# DC075B_ANALOG_INPUTS.net
KiCad netlist of a schematic drawn in Altium Designer
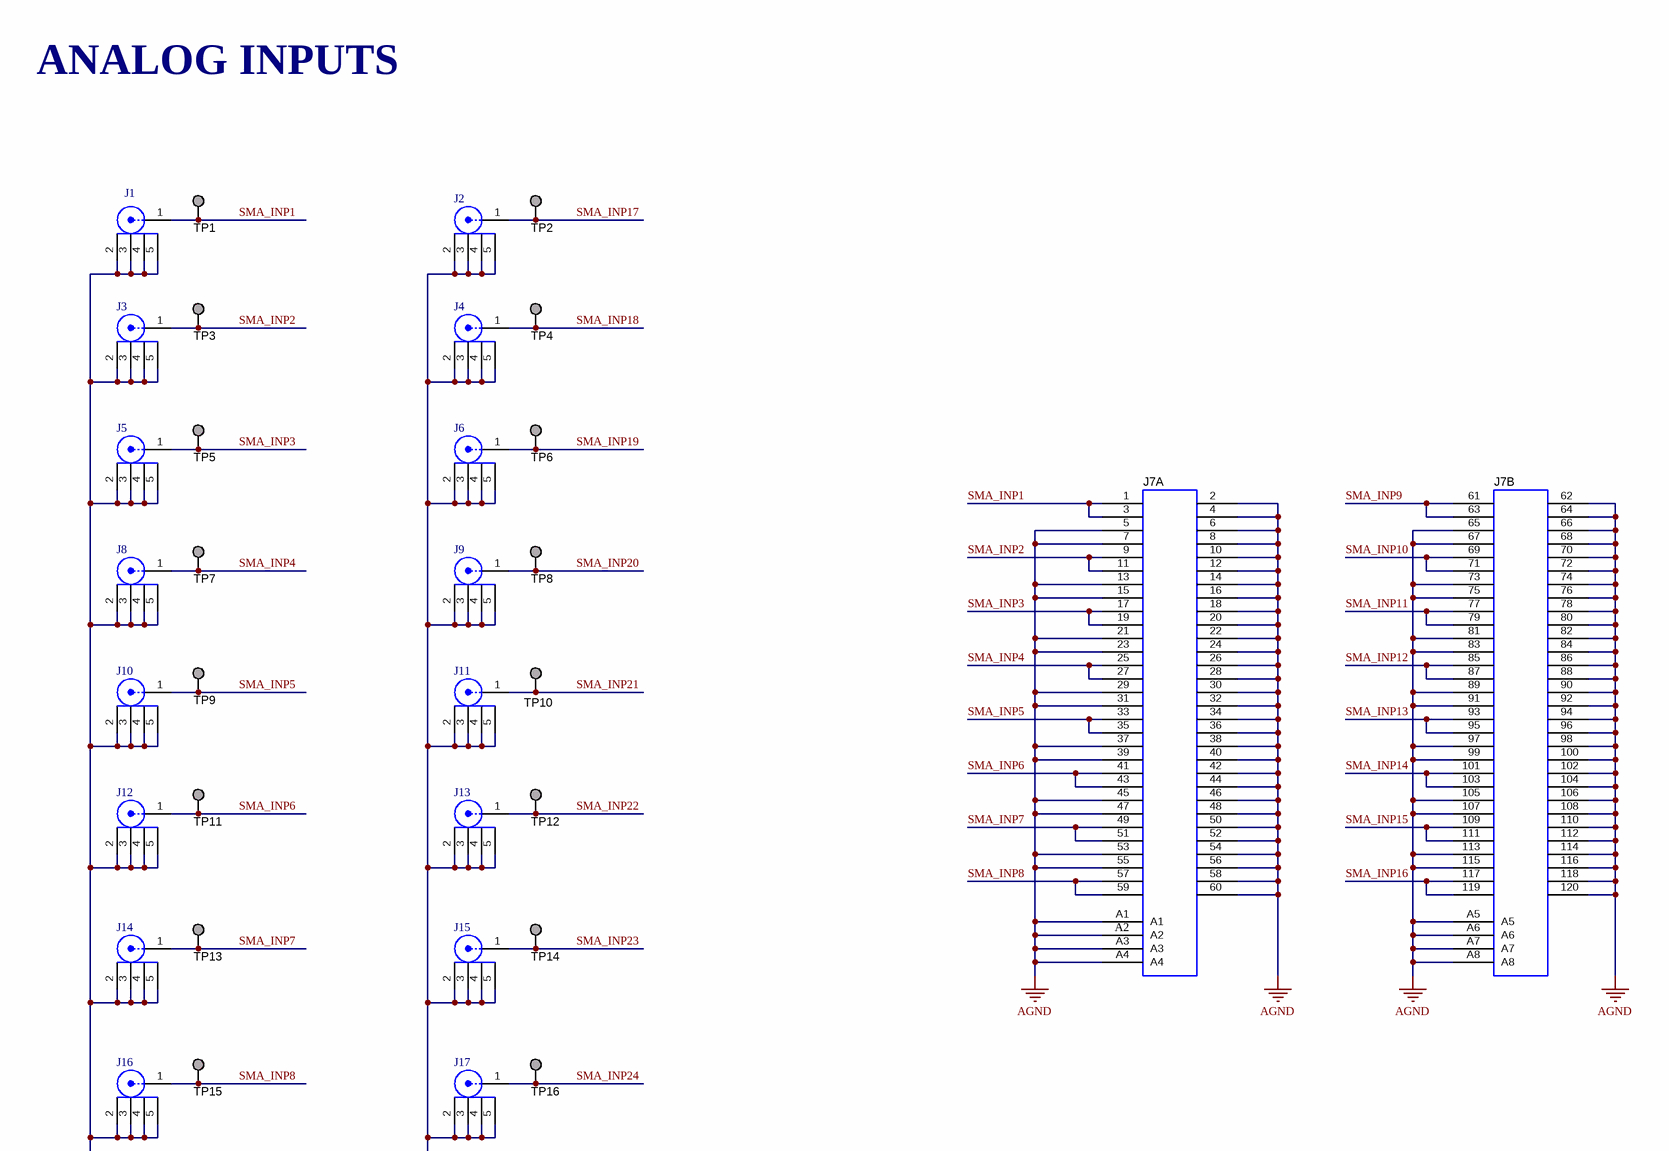
[diagram p0: DC075B_ANALOG_INPUTS.SchDoc, top left]
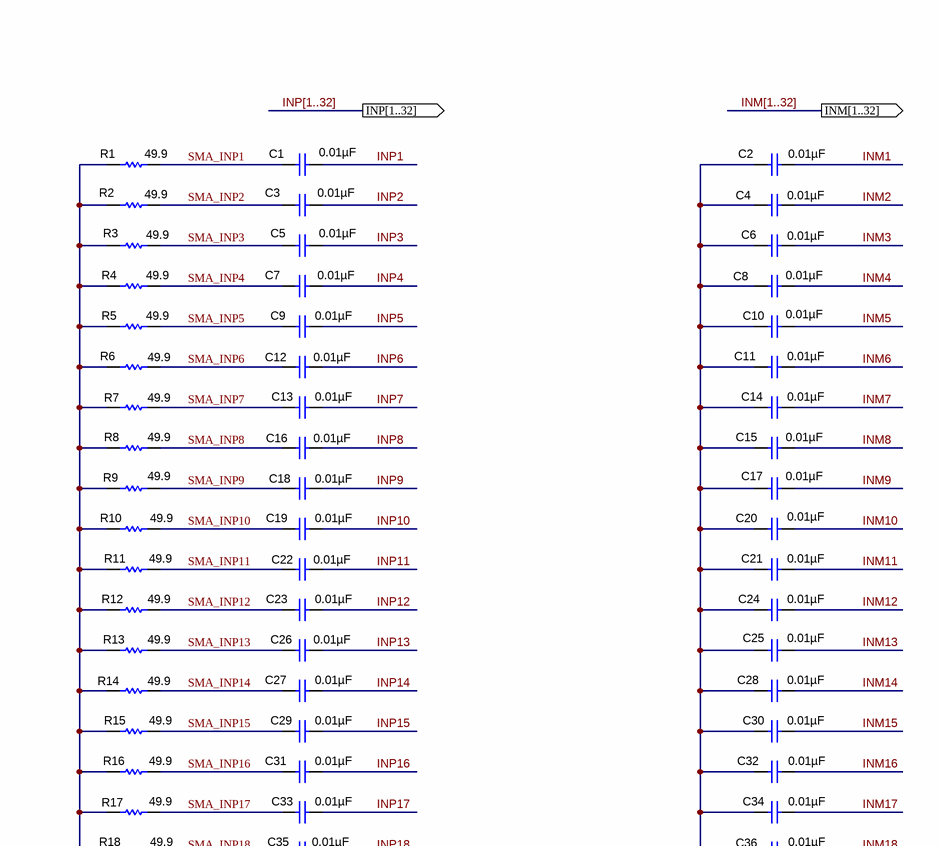
[diagram p1: DC075B_ANALOG_INPUTS.SchDoc, top right]
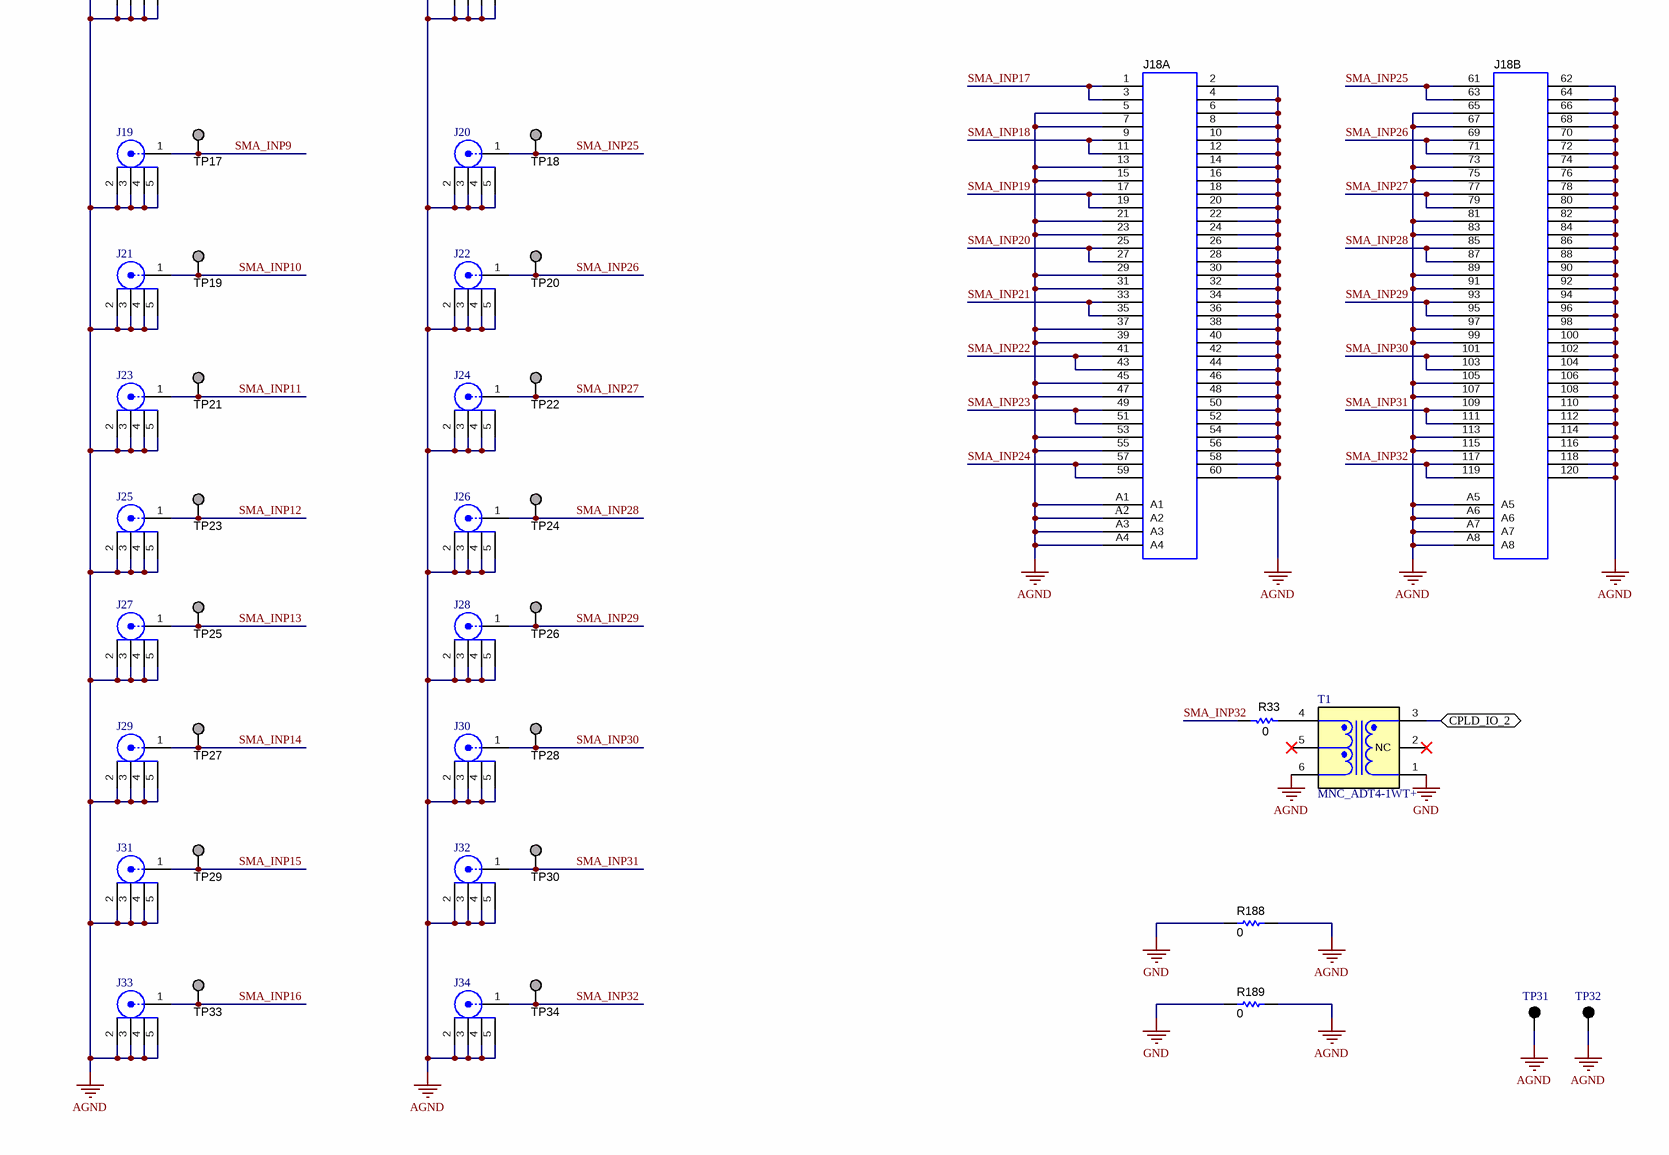
[diagram p2: DC075B_ANALOG_INPUTS.SchDoc, bottom left]
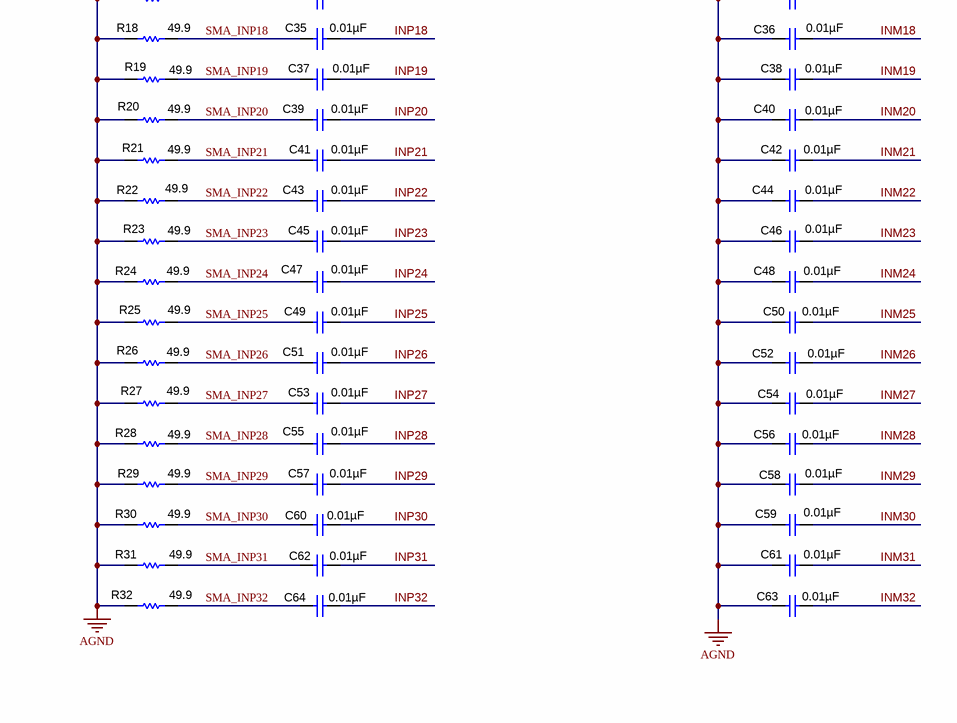
[diagram p3: DC075B_ANALOG_INPUTS.SchDoc, bottom right]

(export (version "E")
  (design (tool "Eeschema 10.0.6"))
  (components
    (comp (ref "C1")
      (value "04023C103JAT2A")
      (footprint "0402")
      (description "CAP, CERM, 0.01 µF, 25 V,+/- 5%, X7R, 0402")
      (fields (field (name "VALUEDISPLAYED") "0.01µF") (field (name "MANUFACTURER") "AVX"))
      (libsource (lib "Altium Vault - TI") (part "Capacitor"))
    )
    (comp (ref "C2")
      (value "04023C103JAT2A")
      (footprint "0402")
      (description "CAP, CERM, 0.01 µF, 25 V,+/- 5%, X7R, 0402")
      (fields (field (name "VALUEDISPLAYED") "0.01µF") (field (name "MANUFACTURER") "AVX"))
      (libsource (lib "Altium Vault - TI") (part "Capacitor"))
    )
    (comp (ref "C3")
      (value "04023C103JAT2A")
      (footprint "0402")
      (description "CAP, CERM, 0.01 µF, 25 V,+/- 5%, X7R, 0402")
      (fields (field (name "VALUEDISPLAYED") "0.01µF") (field (name "MANUFACTURER") "AVX"))
      (libsource (lib "Altium Vault - TI") (part "Capacitor"))
    )
    (comp (ref "C4")
      (value "04023C103JAT2A")
      (footprint "0402")
      (description "CAP, CERM, 0.01 µF, 25 V,+/- 5%, X7R, 0402")
      (fields (field (name "VALUEDISPLAYED") "0.01µF") (field (name "MANUFACTURER") "AVX"))
      (libsource (lib "Altium Vault - TI") (part "Capacitor"))
    )
    (comp (ref "C5")
      (value "04023C103JAT2A")
      (footprint "0402")
      (description "CAP, CERM, 0.01 µF, 25 V,+/- 5%, X7R, 0402")
      (fields (field (name "VALUEDISPLAYED") "0.01µF") (field (name "MANUFACTURER") "AVX"))
      (libsource (lib "Altium Vault - TI") (part "Capacitor"))
    )
    (comp (ref "C6")
      (value "04023C103JAT2A")
      (footprint "0402")
      (description "CAP, CERM, 0.01 µF, 25 V,+/- 5%, X7R, 0402")
      (fields (field (name "VALUEDISPLAYED") "0.01µF") (field (name "MANUFACTURER") "AVX"))
      (libsource (lib "Altium Vault - TI") (part "Capacitor"))
    )
    (comp (ref "C7")
      (value "04023C103JAT2A")
      (footprint "0402")
      (description "CAP, CERM, 0.01 µF, 25 V,+/- 5%, X7R, 0402")
      (fields (field (name "VALUEDISPLAYED") "0.01µF") (field (name "MANUFACTURER") "AVX"))
      (libsource (lib "Altium Vault - TI") (part "Capacitor"))
    )
    (comp (ref "C8")
      (value "04023C103JAT2A")
      (footprint "0402")
      (description "CAP, CERM, 0.01 µF, 25 V,+/- 5%, X7R, 0402")
      (fields (field (name "VALUEDISPLAYED") "0.01µF") (field (name "MANUFACTURER") "AVX"))
      (libsource (lib "Altium Vault - TI") (part "Capacitor"))
    )
    (comp (ref "C9")
      (value "04023C103JAT2A")
      (footprint "0402")
      (description "CAP, CERM, 0.01 µF, 25 V,+/- 5%, X7R, 0402")
      (fields (field (name "VALUEDISPLAYED") "0.01µF") (field (name "MANUFACTURER") "AVX"))
      (libsource (lib "Altium Vault - TI") (part "Capacitor"))
    )
    (comp (ref "C10")
      (value "04023C103JAT2A")
      (footprint "0402")
      (description "CAP, CERM, 0.01 µF, 25 V,+/- 5%, X7R, 0402")
      (fields (field (name "VALUEDISPLAYED") "0.01µF") (field (name "MANUFACTURER") "AVX"))
      (libsource (lib "Altium Vault - TI") (part "Capacitor"))
    )
    (comp (ref "C11")
      (value "04023C103JAT2A")
      (footprint "0402")
      (description "CAP, CERM, 0.01 µF, 25 V,+/- 5%, X7R, 0402")
      (fields (field (name "VALUEDISPLAYED") "0.01µF") (field (name "MANUFACTURER") "AVX"))
      (libsource (lib "Altium Vault - TI") (part "Capacitor"))
    )
    (comp (ref "C12")
      (value "04023C103JAT2A")
      (footprint "0402")
      (description "CAP, CERM, 0.01 µF, 25 V,+/- 5%, X7R, 0402")
      (fields (field (name "VALUEDISPLAYED") "0.01µF") (field (name "MANUFACTURER") "AVX"))
      (libsource (lib "Altium Vault - TI") (part "Capacitor"))
    )
    (comp (ref "C13")
      (value "04023C103JAT2A")
      (footprint "0402")
      (description "CAP, CERM, 0.01 µF, 25 V,+/- 5%, X7R, 0402")
      (fields (field (name "VALUEDISPLAYED") "0.01µF") (field (name "MANUFACTURER") "AVX"))
      (libsource (lib "Altium Vault - TI") (part "Capacitor"))
    )
    (comp (ref "C14")
      (value "04023C103JAT2A")
      (footprint "0402")
      (description "CAP, CERM, 0.01 µF, 25 V,+/- 5%, X7R, 0402")
      (fields (field (name "VALUEDISPLAYED") "0.01µF") (field (name "MANUFACTURER") "AVX"))
      (libsource (lib "Altium Vault - TI") (part "Capacitor"))
    )
    (comp (ref "C15")
      (value "04023C103JAT2A")
      (footprint "0402")
      (description "CAP, CERM, 0.01 µF, 25 V,+/- 5%, X7R, 0402")
      (fields (field (name "VALUEDISPLAYED") "0.01µF") (field (name "MANUFACTURER") "AVX"))
      (libsource (lib "Altium Vault - TI") (part "Capacitor"))
    )
    (comp (ref "C16")
      (value "04023C103JAT2A")
      (footprint "0402")
      (description "CAP, CERM, 0.01 µF, 25 V,+/- 5%, X7R, 0402")
      (fields (field (name "VALUEDISPLAYED") "0.01µF") (field (name "MANUFACTURER") "AVX"))
      (libsource (lib "Altium Vault - TI") (part "Capacitor"))
    )
    (comp (ref "C17")
      (value "04023C103JAT2A")
      (footprint "0402")
      (description "CAP, CERM, 0.01 µF, 25 V,+/- 5%, X7R, 0402")
      (fields (field (name "VALUEDISPLAYED") "0.01µF") (field (name "MANUFACTURER") "AVX"))
      (libsource (lib "Altium Vault - TI") (part "Capacitor"))
    )
    (comp (ref "C18")
      (value "04023C103JAT2A")
      (footprint "0402")
      (description "CAP, CERM, 0.01 µF, 25 V,+/- 5%, X7R, 0402")
      (fields (field (name "VALUEDISPLAYED") "0.01µF") (field (name "MANUFACTURER") "AVX"))
      (libsource (lib "Altium Vault - TI") (part "Capacitor"))
    )
    (comp (ref "C19")
      (value "04023C103JAT2A")
      (footprint "0402")
      (description "CAP, CERM, 0.01 µF, 25 V,+/- 5%, X7R, 0402")
      (fields (field (name "VALUEDISPLAYED") "0.01µF") (field (name "MANUFACTURER") "AVX"))
      (libsource (lib "Altium Vault - TI") (part "Capacitor"))
    )
    (comp (ref "C20")
      (value "04023C103JAT2A")
      (footprint "0402")
      (description "CAP, CERM, 0.01 µF, 25 V,+/- 5%, X7R, 0402")
      (fields (field (name "VALUEDISPLAYED") "0.01µF") (field (name "MANUFACTURER") "AVX"))
      (libsource (lib "Altium Vault - TI") (part "Capacitor"))
    )
    (comp (ref "C21")
      (value "04023C103JAT2A")
      (footprint "0402")
      (description "CAP, CERM, 0.01 µF, 25 V,+/- 5%, X7R, 0402")
      (fields (field (name "VALUEDISPLAYED") "0.01µF") (field (name "MANUFACTURER") "AVX"))
      (libsource (lib "Altium Vault - TI") (part "Capacitor"))
    )
    (comp (ref "C22")
      (value "04023C103JAT2A")
      (footprint "0402")
      (description "CAP, CERM, 0.01 µF, 25 V,+/- 5%, X7R, 0402")
      (fields (field (name "VALUEDISPLAYED") "0.01µF") (field (name "MANUFACTURER") "AVX"))
      (libsource (lib "Altium Vault - TI") (part "Capacitor"))
    )
    (comp (ref "C23")
      (value "04023C103JAT2A")
      (footprint "0402")
      (description "CAP, CERM, 0.01 µF, 25 V,+/- 5%, X7R, 0402")
      (fields (field (name "VALUEDISPLAYED") "0.01µF") (field (name "MANUFACTURER") "AVX"))
      (libsource (lib "Altium Vault - TI") (part "Capacitor"))
    )
    (comp (ref "C24")
      (value "04023C103JAT2A")
      (footprint "0402")
      (description "CAP, CERM, 0.01 µF, 25 V,+/- 5%, X7R, 0402")
      (fields (field (name "VALUEDISPLAYED") "0.01µF") (field (name "MANUFACTURER") "AVX"))
      (libsource (lib "Altium Vault - TI") (part "Capacitor"))
    )
    (comp (ref "C25")
      (value "04023C103JAT2A")
      (footprint "0402")
      (description "CAP, CERM, 0.01 µF, 25 V,+/- 5%, X7R, 0402")
      (fields (field (name "VALUEDISPLAYED") "0.01µF") (field (name "MANUFACTURER") "AVX"))
      (libsource (lib "Altium Vault - TI") (part "Capacitor"))
    )
    (comp (ref "C26")
      (value "04023C103JAT2A")
      (footprint "0402")
      (description "CAP, CERM, 0.01 µF, 25 V,+/- 5%, X7R, 0402")
      (fields (field (name "VALUEDISPLAYED") "0.01µF") (field (name "MANUFACTURER") "AVX"))
      (libsource (lib "Altium Vault - TI") (part "Capacitor"))
    )
    (comp (ref "C27")
      (value "04023C103JAT2A")
      (footprint "0402")
      (description "CAP, CERM, 0.01 µF, 25 V,+/- 5%, X7R, 0402")
      (fields (field (name "VALUEDISPLAYED") "0.01µF") (field (name "MANUFACTURER") "AVX"))
      (libsource (lib "Altium Vault - TI") (part "Capacitor"))
    )
    (comp (ref "C28")
      (value "04023C103JAT2A")
      (footprint "0402")
      (description "CAP, CERM, 0.01 µF, 25 V,+/- 5%, X7R, 0402")
      (fields (field (name "VALUEDISPLAYED") "0.01µF") (field (name "MANUFACTURER") "AVX"))
      (libsource (lib "Altium Vault - TI") (part "Capacitor"))
    )
    (comp (ref "C29")
      (value "04023C103JAT2A")
      (footprint "0402")
      (description "CAP, CERM, 0.01 µF, 25 V,+/- 5%, X7R, 0402")
      (fields (field (name "VALUEDISPLAYED") "0.01µF") (field (name "MANUFACTURER") "AVX"))
      (libsource (lib "Altium Vault - TI") (part "Capacitor"))
    )
    (comp (ref "C30")
      (value "04023C103JAT2A")
      (footprint "0402")
      (description "CAP, CERM, 0.01 µF, 25 V,+/- 5%, X7R, 0402")
      (fields (field (name "VALUEDISPLAYED") "0.01µF") (field (name "MANUFACTURER") "AVX"))
      (libsource (lib "Altium Vault - TI") (part "Capacitor"))
    )
    (comp (ref "C31")
      (value "04023C103JAT2A")
      (footprint "0402")
      (description "CAP, CERM, 0.01 µF, 25 V,+/- 5%, X7R, 0402")
      (fields (field (name "VALUEDISPLAYED") "0.01µF") (field (name "MANUFACTURER") "AVX"))
      (libsource (lib "Altium Vault - TI") (part "Capacitor"))
    )
    (comp (ref "C32")
      (value "04023C103JAT2A")
      (footprint "0402")
      (description "CAP, CERM, 0.01 µF, 25 V,+/- 5%, X7R, 0402")
      (fields (field (name "VALUEDISPLAYED") "0.01µF") (field (name "MANUFACTURER") "AVX"))
      (libsource (lib "Altium Vault - TI") (part "Capacitor"))
    )
    (comp (ref "C33")
      (value "04023C103JAT2A")
      (footprint "0402")
      (description "CAP, CERM, 0.01 µF, 25 V,+/- 5%, X7R, 0402")
      (fields (field (name "VALUEDISPLAYED") "0.01µF") (field (name "MANUFACTURER") "AVX"))
      (libsource (lib "Altium Vault - TI") (part "Capacitor"))
    )
    (comp (ref "C34")
      (value "04023C103JAT2A")
      (footprint "0402")
      (description "CAP, CERM, 0.01 µF, 25 V,+/- 5%, X7R, 0402")
      (fields (field (name "VALUEDISPLAYED") "0.01µF") (field (name "MANUFACTURER") "AVX"))
      (libsource (lib "Altium Vault - TI") (part "Capacitor"))
    )
    (comp (ref "C35")
      (value "04023C103JAT2A")
      (footprint "0402")
      (description "CAP, CERM, 0.01 µF, 25 V,+/- 5%, X7R, 0402")
      (fields (field (name "VALUEDISPLAYED") "0.01µF") (field (name "MANUFACTURER") "AVX"))
      (libsource (lib "Altium Vault - TI") (part "Capacitor"))
    )
    (comp (ref "C36")
      (value "04023C103JAT2A")
      (footprint "0402")
      (description "CAP, CERM, 0.01 µF, 25 V,+/- 5%, X7R, 0402")
      (fields (field (name "VALUEDISPLAYED") "0.01µF") (field (name "MANUFACTURER") "AVX"))
      (libsource (lib "Altium Vault - TI") (part "Capacitor"))
    )
    (comp (ref "C37")
      (value "04023C103JAT2A")
      (footprint "0402")
      (description "CAP, CERM, 0.01 µF, 25 V,+/- 5%, X7R, 0402")
      (fields (field (name "VALUEDISPLAYED") "0.01µF") (field (name "MANUFACTURER") "AVX"))
      (libsource (lib "Altium Vault - TI") (part "Capacitor"))
    )
    (comp (ref "C38")
      (value "04023C103JAT2A")
      (footprint "0402")
      (description "CAP, CERM, 0.01 µF, 25 V,+/- 5%, X7R, 0402")
      (fields (field (name "VALUEDISPLAYED") "0.01µF") (field (name "MANUFACTURER") "AVX"))
      (libsource (lib "Altium Vault - TI") (part "Capacitor"))
    )
    (comp (ref "C39")
      (value "04023C103JAT2A")
      (footprint "0402")
      (description "CAP, CERM, 0.01 µF, 25 V,+/- 5%, X7R, 0402")
      (fields (field (name "VALUEDISPLAYED") "0.01µF") (field (name "MANUFACTURER") "AVX"))
      (libsource (lib "Altium Vault - TI") (part "Capacitor"))
    )
    (comp (ref "C40")
      (value "04023C103JAT2A")
      (footprint "0402")
      (description "CAP, CERM, 0.01 µF, 25 V,+/- 5%, X7R, 0402")
      (fields (field (name "VALUEDISPLAYED") "0.01µF") (field (name "MANUFACTURER") "AVX"))
      (libsource (lib "Altium Vault - TI") (part "Capacitor"))
    )
    (comp (ref "C41")
      (value "04023C103JAT2A")
      (footprint "0402")
      (description "CAP, CERM, 0.01 µF, 25 V,+/- 5%, X7R, 0402")
      (fields (field (name "VALUEDISPLAYED") "0.01µF") (field (name "MANUFACTURER") "AVX"))
      (libsource (lib "Altium Vault - TI") (part "Capacitor"))
    )
    (comp (ref "C42")
      (value "04023C103JAT2A")
      (footprint "0402")
      (description "CAP, CERM, 0.01 µF, 25 V,+/- 5%, X7R, 0402")
      (fields (field (name "VALUEDISPLAYED") "0.01µF") (field (name "MANUFACTURER") "AVX"))
      (libsource (lib "Altium Vault - TI") (part "Capacitor"))
    )
    (comp (ref "C43")
      (value "04023C103JAT2A")
      (footprint "0402")
      (description "CAP, CERM, 0.01 µF, 25 V,+/- 5%, X7R, 0402")
      (fields (field (name "VALUEDISPLAYED") "0.01µF") (field (name "MANUFACTURER") "AVX"))
      (libsource (lib "Altium Vault - TI") (part "Capacitor"))
    )
    (comp (ref "C44")
      (value "04023C103JAT2A")
      (footprint "0402")
      (description "CAP, CERM, 0.01 µF, 25 V,+/- 5%, X7R, 0402")
      (fields (field (name "VALUEDISPLAYED") "0.01µF") (field (name "MANUFACTURER") "AVX"))
      (libsource (lib "Altium Vault - TI") (part "Capacitor"))
    )
    (comp (ref "C45")
      (value "04023C103JAT2A")
      (footprint "0402")
      (description "CAP, CERM, 0.01 µF, 25 V,+/- 5%, X7R, 0402")
      (fields (field (name "VALUEDISPLAYED") "0.01µF") (field (name "MANUFACTURER") "AVX"))
      (libsource (lib "Altium Vault - TI") (part "Capacitor"))
    )
    (comp (ref "C46")
      (value "04023C103JAT2A")
      (footprint "0402")
      (description "CAP, CERM, 0.01 µF, 25 V,+/- 5%, X7R, 0402")
      (fields (field (name "VALUEDISPLAYED") "0.01µF") (field (name "MANUFACTURER") "AVX"))
      (libsource (lib "Altium Vault - TI") (part "Capacitor"))
    )
    (comp (ref "C47")
      (value "04023C103JAT2A")
      (footprint "0402")
      (description "CAP, CERM, 0.01 µF, 25 V,+/- 5%, X7R, 0402")
      (fields (field (name "VALUEDISPLAYED") "0.01µF") (field (name "MANUFACTURER") "AVX"))
      (libsource (lib "Altium Vault - TI") (part "Capacitor"))
    )
    (comp (ref "C48")
      (value "04023C103JAT2A")
      (footprint "0402")
      (description "CAP, CERM, 0.01 µF, 25 V,+/- 5%, X7R, 0402")
      (fields (field (name "VALUEDISPLAYED") "0.01µF") (field (name "MANUFACTURER") "AVX"))
      (libsource (lib "Altium Vault - TI") (part "Capacitor"))
    )
    (comp (ref "C49")
      (value "04023C103JAT2A")
      (footprint "0402")
      (description "CAP, CERM, 0.01 µF, 25 V,+/- 5%, X7R, 0402")
      (fields (field (name "VALUEDISPLAYED") "0.01µF") (field (name "MANUFACTURER") "AVX"))
      (libsource (lib "Altium Vault - TI") (part "Capacitor"))
    )
    (comp (ref "C50")
      (value "04023C103JAT2A")
      (footprint "0402")
      (description "CAP, CERM, 0.01 µF, 25 V,+/- 5%, X7R, 0402")
      (fields (field (name "VALUEDISPLAYED") "0.01µF") (field (name "MANUFACTURER") "AVX"))
      (libsource (lib "Altium Vault - TI") (part "Capacitor"))
    )
    (comp (ref "C51")
      (value "04023C103JAT2A")
      (footprint "0402")
      (description "CAP, CERM, 0.01 µF, 25 V,+/- 5%, X7R, 0402")
      (fields (field (name "VALUEDISPLAYED") "0.01µF") (field (name "MANUFACTURER") "AVX"))
      (libsource (lib "Altium Vault - TI") (part "Capacitor"))
    )
    (comp (ref "C52")
      (value "04023C103JAT2A")
      (footprint "0402")
      (description "CAP, CERM, 0.01 µF, 25 V,+/- 5%, X7R, 0402")
      (fields (field (name "VALUEDISPLAYED") "0.01µF") (field (name "MANUFACTURER") "AVX"))
      (libsource (lib "Altium Vault - TI") (part "Capacitor"))
    )
    (comp (ref "C53")
      (value "04023C103JAT2A")
      (footprint "0402")
      (description "CAP, CERM, 0.01 µF, 25 V,+/- 5%, X7R, 0402")
      (fields (field (name "VALUEDISPLAYED") "0.01µF") (field (name "MANUFACTURER") "AVX"))
      (libsource (lib "Altium Vault - TI") (part "Capacitor"))
    )
    (comp (ref "C54")
      (value "04023C103JAT2A")
      (footprint "0402")
      (description "CAP, CERM, 0.01 µF, 25 V,+/- 5%, X7R, 0402")
      (fields (field (name "VALUEDISPLAYED") "0.01µF") (field (name "MANUFACTURER") "AVX"))
      (libsource (lib "Altium Vault - TI") (part "Capacitor"))
    )
    (comp (ref "C55")
      (value "04023C103JAT2A")
      (footprint "0402")
      (description "CAP, CERM, 0.01 µF, 25 V,+/- 5%, X7R, 0402")
      (fields (field (name "VALUEDISPLAYED") "0.01µF") (field (name "MANUFACTURER") "AVX"))
      (libsource (lib "Altium Vault - TI") (part "Capacitor"))
    )
    (comp (ref "C56")
      (value "04023C103JAT2A")
      (footprint "0402")
      (description "CAP, CERM, 0.01 µF, 25 V,+/- 5%, X7R, 0402")
      (fields (field (name "VALUEDISPLAYED") "0.01µF") (field (name "MANUFACTURER") "AVX"))
      (libsource (lib "Altium Vault - TI") (part "Capacitor"))
    )
    (comp (ref "C57")
      (value "04023C103JAT2A")
      (footprint "0402")
      (description "CAP, CERM, 0.01 µF, 25 V,+/- 5%, X7R, 0402")
      (fields (field (name "VALUEDISPLAYED") "0.01µF") (field (name "MANUFACTURER") "AVX"))
      (libsource (lib "Altium Vault - TI") (part "Capacitor"))
    )
    (comp (ref "C58")
      (value "04023C103JAT2A")
      (footprint "0402")
      (description "CAP, CERM, 0.01 µF, 25 V,+/- 5%, X7R, 0402")
      (fields (field (name "VALUEDISPLAYED") "0.01µF") (field (name "MANUFACTURER") "AVX"))
      (libsource (lib "Altium Vault - TI") (part "Capacitor"))
    )
    (comp (ref "C59")
      (value "04023C103JAT2A")
      (footprint "0402")
      (description "CAP, CERM, 0.01 µF, 25 V,+/- 5%, X7R, 0402")
      (fields (field (name "VALUEDISPLAYED") "0.01µF") (field (name "MANUFACTURER") "AVX"))
      (libsource (lib "Altium Vault - TI") (part "Capacitor"))
    )
    (comp (ref "C60")
      (value "04023C103JAT2A")
      (footprint "0402")
      (description "CAP, CERM, 0.01 µF, 25 V,+/- 5%, X7R, 0402")
      (fields (field (name "VALUEDISPLAYED") "0.01µF") (field (name "MANUFACTURER") "AVX"))
      (libsource (lib "Altium Vault - TI") (part "Capacitor"))
    )
    (comp (ref "C61")
      (value "04023C103JAT2A")
      (footprint "0402")
      (description "CAP, CERM, 0.01 µF, 25 V,+/- 5%, X7R, 0402")
      (fields (field (name "VALUEDISPLAYED") "0.01µF") (field (name "MANUFACTURER") "AVX"))
      (libsource (lib "Altium Vault - TI") (part "Capacitor"))
    )
    (comp (ref "C62")
      (value "04023C103JAT2A")
      (footprint "0402")
      (description "CAP, CERM, 0.01 µF, 25 V,+/- 5%, X7R, 0402")
      (fields (field (name "VALUEDISPLAYED") "0.01µF") (field (name "MANUFACTURER") "AVX"))
      (libsource (lib "Altium Vault - TI") (part "Capacitor"))
    )
    (comp (ref "C63")
      (value "04023C103JAT2A")
      (footprint "0402")
      (description "CAP, CERM, 0.01 µF, 25 V,+/- 5%, X7R, 0402")
      (fields (field (name "VALUEDISPLAYED") "0.01µF") (field (name "MANUFACTURER") "AVX"))
      (libsource (lib "Altium Vault - TI") (part "Capacitor"))
    )
    (comp (ref "C64")
      (value "04023C103JAT2A")
      (footprint "0402")
      (description "CAP, CERM, 0.01 µF, 25 V,+/- 5%, X7R, 0402")
      (fields (field (name "VALUEDISPLAYED") "0.01µF") (field (name "MANUFACTURER") "AVX"))
      (libsource (lib "Altium Vault - TI") (part "Capacitor"))
    )
    (comp (ref "J1")
      (value "SMA_Contact1_GND2345")
      (footprint "Johnson_142-0701-801")
      (description "Connector, End launch SMA, 50 ohm, SMT")
      (fields
        (field (name "PARTNUMBER") "142-0701-801")
        (field (name "MANUFACTURER") "Cinch Connectivity")
        (field (name "PUBLISHER") "Texas Instruments")
      )
      (libsource (lib "Altium Vault - TI") (part "SMA_Contact1_GND2345"))
    )
    (comp (ref "J2")
      (value "5-1814832-1")
      (footprint "TE_5-1814832-1")
      (description "SMA Straight PCB Socket Die Cast, 50 Ohm, TH")
      (fields (field (name "MANUFACTURER") "TE Connectivity") (field (name "PUBLISHER") "Texas Instruments"))
      (libsource (lib "Altium Vault - TI") (part "SMA_Contact1_GND2345"))
    )
    (comp (ref "J3")
      (value "5-1814832-1")
      (footprint "TE_5-1814832-1")
      (description "SMA Straight PCB Socket Die Cast, 50 Ohm, TH")
      (fields (field (name "MANUFACTURER") "TE Connectivity") (field (name "PUBLISHER") "Texas Instruments"))
      (libsource (lib "Altium Vault - TI") (part "SMA_Contact1_GND2345"))
    )
    (comp (ref "J4")
      (value "SMA_Contact1_GND2345")
      (footprint "Johnson_142-0701-801")
      (description "Connector, End launch SMA, 50 ohm, SMT")
      (fields
        (field (name "PARTNUMBER") "142-0701-801")
        (field (name "MANUFACTURER") "Cinch Connectivity")
        (field (name "PUBLISHER") "Texas Instruments")
      )
      (libsource (lib "Altium Vault - TI") (part "SMA_Contact1_GND2345"))
    )
    (comp (ref "J5")
      (value "5-1814832-1")
      (footprint "TE_5-1814832-1")
      (description "SMA Straight PCB Socket Die Cast, 50 Ohm, TH")
      (fields (field (name "MANUFACTURER") "TE Connectivity") (field (name "PUBLISHER") "Texas Instruments"))
      (libsource (lib "Altium Vault - TI") (part "SMA_Contact1_GND2345"))
    )
    (comp (ref "J6")
      (value "5-1814832-1")
      (footprint "TE_5-1814832-1")
      (description "SMA Straight PCB Socket Die Cast, 50 Ohm, TH")
      (fields (field (name "MANUFACTURER") "TE Connectivity") (field (name "PUBLISHER") "Texas Instruments"))
      (libsource (lib "Altium Vault - TI") (part "SMA_Contact1_GND2345"))
    )
    (comp (ref "J7")
      (value "SAMTEC_QTH-060-01-L-D-A")
      (footprint "SAMTEC_QTH-060-01-L-D-A")
      (description "Socket, 0.5MM, 60x2, Gold, SMT")
      (fields (field (name "PARTNUMBER") "QTH-060-01-L-D-A") (field (name "MANUFACTURER") "Samtec"))
      (libsource (lib "Altium Vault - TI") (part "CMP-0056023-2"))
    )
    (comp (ref "J8")
      (value "SMA_Contact1_GND2345")
      (footprint "Johnson_142-0701-801")
      (description "Connector, End launch SMA, 50 ohm, SMT")
      (fields
        (field (name "PARTNUMBER") "142-0701-801")
        (field (name "MANUFACTURER") "Cinch Connectivity")
        (field (name "PUBLISHER") "Texas Instruments")
      )
      (libsource (lib "Altium Vault - TI") (part "SMA_Contact1_GND2345"))
    )
    (comp (ref "J9")
      (value "5-1814832-1")
      (footprint "TE_5-1814832-1")
      (description "SMA Straight PCB Socket Die Cast, 50 Ohm, TH")
      (fields (field (name "MANUFACTURER") "TE Connectivity") (field (name "PUBLISHER") "Texas Instruments"))
      (libsource (lib "Altium Vault - TI") (part "SMA_Contact1_GND2345"))
    )
    (comp (ref "J10")
      (value "5-1814832-1")
      (footprint "TE_5-1814832-1")
      (description "SMA Straight PCB Socket Die Cast, 50 Ohm, TH")
      (fields (field (name "MANUFACTURER") "TE Connectivity") (field (name "PUBLISHER") "Texas Instruments"))
      (libsource (lib "Altium Vault - TI") (part "SMA_Contact1_GND2345"))
    )
    (comp (ref "J11")
      (value "SMA_Contact1_GND2345")
      (footprint "Johnson_142-0701-801")
      (description "Connector, End launch SMA, 50 ohm, SMT")
      (fields
        (field (name "PARTNUMBER") "142-0701-801")
        (field (name "MANUFACTURER") "Cinch Connectivity")
        (field (name "PUBLISHER") "Texas Instruments")
      )
      (libsource (lib "Altium Vault - TI") (part "SMA_Contact1_GND2345"))
    )
    (comp (ref "J12")
      (value "5-1814832-1")
      (footprint "TE_5-1814832-1")
      (description "SMA Straight PCB Socket Die Cast, 50 Ohm, TH")
      (fields (field (name "MANUFACTURER") "TE Connectivity") (field (name "PUBLISHER") "Texas Instruments"))
      (libsource (lib "Altium Vault - TI") (part "SMA_Contact1_GND2345"))
    )
    (comp (ref "J13")
      (value "5-1814832-1")
      (footprint "TE_5-1814832-1")
      (description "SMA Straight PCB Socket Die Cast, 50 Ohm, TH")
      (fields (field (name "MANUFACTURER") "TE Connectivity") (field (name "PUBLISHER") "Texas Instruments"))
      (libsource (lib "Altium Vault - TI") (part "SMA_Contact1_GND2345"))
    )
    (comp (ref "J14")
      (value "SMA_Contact1_GND2345")
      (footprint "Johnson_142-0701-801")
      (description "Connector, End launch SMA, 50 ohm, SMT")
      (fields
        (field (name "PARTNUMBER") "142-0701-801")
        (field (name "MANUFACTURER") "Cinch Connectivity")
        (field (name "PUBLISHER") "Texas Instruments")
      )
      (libsource (lib "Altium Vault - TI") (part "SMA_Contact1_GND2345"))
    )
    (comp (ref "J15")
      (value "5-1814832-1")
      (footprint "TE_5-1814832-1")
      (description "SMA Straight PCB Socket Die Cast, 50 Ohm, TH")
      (fields (field (name "MANUFACTURER") "TE Connectivity") (field (name "PUBLISHER") "Texas Instruments"))
      (libsource (lib "Altium Vault - TI") (part "SMA_Contact1_GND2345"))
    )
    (comp (ref "J16")
      (value "5-1814832-1")
      (footprint "TE_5-1814832-1")
      (description "SMA Straight PCB Socket Die Cast, 50 Ohm, TH")
      (fields (field (name "MANUFACTURER") "TE Connectivity") (field (name "PUBLISHER") "Texas Instruments"))
      (libsource (lib "Altium Vault - TI") (part "SMA_Contact1_GND2345"))
    )
    (comp (ref "J17")
      (value "SMA_Contact1_GND2345")
      (footprint "Johnson_142-0701-801")
      (description "Connector, End launch SMA, 50 ohm, SMT")
      (fields
        (field (name "PARTNUMBER") "142-0701-801")
        (field (name "MANUFACTURER") "Cinch Connectivity")
        (field (name "PUBLISHER") "Texas Instruments")
      )
      (libsource (lib "Altium Vault - TI") (part "SMA_Contact1_GND2345"))
    )
    (comp (ref "J18")
      (value "SAMTEC_QTH-060-01-L-D-A")
      (footprint "SAMTEC_QTH-060-01-L-D-A")
      (description "Socket, 0.5MM, 60x2, Gold, SMT")
      (fields (field (name "PARTNUMBER") "QTH-060-01-L-D-A") (field (name "MANUFACTURER") "Samtec"))
      (libsource (lib "Altium Vault - TI") (part "CMP-0056023-2"))
    )
    (comp (ref "J19")
      (value "5-1814832-1")
      (footprint "TE_5-1814832-1")
      (description "SMA Straight PCB Socket Die Cast, 50 Ohm, TH")
      (fields (field (name "MANUFACTURER") "TE Connectivity") (field (name "PUBLISHER") "Texas Instruments"))
      (libsource (lib "Altium Vault - TI") (part "SMA_Contact1_GND2345"))
    )
    (comp (ref "J20")
      (value "5-1814832-1")
      (footprint "TE_5-1814832-1")
      (description "SMA Straight PCB Socket Die Cast, 50 Ohm, TH")
      (fields (field (name "MANUFACTURER") "TE Connectivity") (field (name "PUBLISHER") "Texas Instruments"))
      (libsource (lib "Altium Vault - TI") (part "SMA_Contact1_GND2345"))
    )
    (comp (ref "J21")
      (value "SMA_Contact1_GND2345")
      (footprint "Johnson_142-0701-801")
      (description "Connector, End launch SMA, 50 ohm, SMT")
      (fields
        (field (name "PARTNUMBER") "142-0701-801")
        (field (name "MANUFACTURER") "Cinch Connectivity")
        (field (name "PUBLISHER") "Texas Instruments")
      )
      (libsource (lib "Altium Vault - TI") (part "SMA_Contact1_GND2345"))
    )
    (comp (ref "J22")
      (value "5-1814832-1")
      (footprint "TE_5-1814832-1")
      (description "SMA Straight PCB Socket Die Cast, 50 Ohm, TH")
      (fields (field (name "MANUFACTURER") "TE Connectivity") (field (name "PUBLISHER") "Texas Instruments"))
      (libsource (lib "Altium Vault - TI") (part "SMA_Contact1_GND2345"))
    )
    (comp (ref "J23")
      (value "5-1814832-1")
      (footprint "TE_5-1814832-1")
      (description "SMA Straight PCB Socket Die Cast, 50 Ohm, TH")
      (fields (field (name "MANUFACTURER") "TE Connectivity") (field (name "PUBLISHER") "Texas Instruments"))
      (libsource (lib "Altium Vault - TI") (part "SMA_Contact1_GND2345"))
    )
    (comp (ref "J24")
      (value "SMA_Contact1_GND2345")
      (footprint "Johnson_142-0701-801")
      (description "Connector, End launch SMA, 50 ohm, SMT")
      (fields
        (field (name "PARTNUMBER") "142-0701-801")
        (field (name "MANUFACTURER") "Cinch Connectivity")
        (field (name "PUBLISHER") "Texas Instruments")
      )
      (libsource (lib "Altium Vault - TI") (part "SMA_Contact1_GND2345"))
    )
    (comp (ref "J25")
      (value "5-1814832-1")
      (footprint "TE_5-1814832-1")
      (description "SMA Straight PCB Socket Die Cast, 50 Ohm, TH")
      (fields (field (name "MANUFACTURER") "TE Connectivity") (field (name "PUBLISHER") "Texas Instruments"))
      (libsource (lib "Altium Vault - TI") (part "SMA_Contact1_GND2345"))
    )
    (comp (ref "J26")
      (value "5-1814832-1")
      (footprint "TE_5-1814832-1")
      (description "SMA Straight PCB Socket Die Cast, 50 Ohm, TH")
      (fields (field (name "MANUFACTURER") "TE Connectivity") (field (name "PUBLISHER") "Texas Instruments"))
      (libsource (lib "Altium Vault - TI") (part "SMA_Contact1_GND2345"))
    )
    (comp (ref "J27")
      (value "SMA_Contact1_GND2345")
      (footprint "Johnson_142-0701-801")
      (description "Connector, End launch SMA, 50 ohm, SMT")
      (fields
        (field (name "PARTNUMBER") "142-0701-801")
        (field (name "MANUFACTURER") "Cinch Connectivity")
        (field (name "PUBLISHER") "Texas Instruments")
      )
      (libsource (lib "Altium Vault - TI") (part "SMA_Contact1_GND2345"))
    )
    (comp (ref "J28")
      (value "5-1814832-1")
      (footprint "TE_5-1814832-1")
      (description "SMA Straight PCB Socket Die Cast, 50 Ohm, TH")
      (fields (field (name "MANUFACTURER") "TE Connectivity") (field (name "PUBLISHER") "Texas Instruments"))
      (libsource (lib "Altium Vault - TI") (part "SMA_Contact1_GND2345"))
    )
    (comp (ref "J29")
      (value "5-1814832-1")
      (footprint "TE_5-1814832-1")
      (description "SMA Straight PCB Socket Die Cast, 50 Ohm, TH")
      (fields (field (name "MANUFACTURER") "TE Connectivity") (field (name "PUBLISHER") "Texas Instruments"))
      (libsource (lib "Altium Vault - TI") (part "SMA_Contact1_GND2345"))
    )
    (comp (ref "J30")
      (value "SMA_Contact1_GND2345")
      (footprint "Johnson_142-0701-801")
      (description "Connector, End launch SMA, 50 ohm, SMT")
      (fields
        (field (name "PARTNUMBER") "142-0701-801")
        (field (name "MANUFACTURER") "Cinch Connectivity")
        (field (name "PUBLISHER") "Texas Instruments")
      )
      (libsource (lib "Altium Vault - TI") (part "SMA_Contact1_GND2345"))
    )
    (comp (ref "J31")
      (value "5-1814832-1")
      (footprint "TE_5-1814832-1")
      (description "SMA Straight PCB Socket Die Cast, 50 Ohm, TH")
      (fields (field (name "MANUFACTURER") "TE Connectivity") (field (name "PUBLISHER") "Texas Instruments"))
      (libsource (lib "Altium Vault - TI") (part "SMA_Contact1_GND2345"))
    )
    (comp (ref "J32")
      (value "5-1814832-1")
      (footprint "TE_5-1814832-1")
      (description "SMA Straight PCB Socket Die Cast, 50 Ohm, TH")
      (fields (field (name "MANUFACTURER") "TE Connectivity") (field (name "PUBLISHER") "Texas Instruments"))
      (libsource (lib "Altium Vault - TI") (part "SMA_Contact1_GND2345"))
    )
    (comp (ref "J33")
      (value "5-1814832-1")
      (footprint "TE_5-1814832-1")
      (description "SMA Straight PCB Socket Die Cast, 50 Ohm, TH")
      (fields (field (name "MANUFACTURER") "TE Connectivity") (field (name "PUBLISHER") "Texas Instruments"))
      (libsource (lib "Altium Vault - TI") (part "SMA_Contact1_GND2345"))
    )
    (comp (ref "J34")
      (value "5-1814832-1")
      (footprint "TE_5-1814832-1")
      (description "SMA Straight PCB Socket Die Cast, 50 Ohm, TH")
      (fields (field (name "MANUFACTURER") "TE Connectivity") (field (name "PUBLISHER") "Texas Instruments"))
      (libsource (lib "Altium Vault - TI") (part "SMA_Contact1_GND2345"))
    )
    (comp (ref "R1")
      (value "49.9")
      (footprint "0402")
      (description "RES, 49.9, 1%, 0.063 W, AEC-Q200 Grade 0, 0402")
      (fields (field (name "MANUFACTURER") "Vishay-Dale") (field (name "PARTNUMBER") "CRCW040249R9FKED"))
      (libsource (lib "Altium Vault - TI") (part "Resistor"))
    )
    (comp (ref "R2")
      (value "49.9")
      (footprint "0402")
      (description "RES, 49.9, 1%, 0.063 W, AEC-Q200 Grade 0, 0402")
      (fields (field (name "MANUFACTURER") "Vishay-Dale") (field (name "PARTNUMBER") "CRCW040249R9FKED"))
      (libsource (lib "Altium Vault - TI") (part "Resistor"))
    )
    (comp (ref "R3")
      (value "49.9")
      (footprint "0402")
      (description "RES, 49.9, 1%, 0.063 W, AEC-Q200 Grade 0, 0402")
      (fields (field (name "MANUFACTURER") "Vishay-Dale") (field (name "PARTNUMBER") "CRCW040249R9FKED"))
      (libsource (lib "Altium Vault - TI") (part "Resistor"))
    )
    (comp (ref "R4")
      (value "49.9")
      (footprint "0402")
      (description "RES, 49.9, 1%, 0.063 W, AEC-Q200 Grade 0, 0402")
      (fields (field (name "MANUFACTURER") "Vishay-Dale") (field (name "PARTNUMBER") "CRCW040249R9FKED"))
      (libsource (lib "Altium Vault - TI") (part "Resistor"))
    )
    (comp (ref "R5")
      (value "49.9")
      (footprint "0402")
      (description "RES, 49.9, 1%, 0.063 W, AEC-Q200 Grade 0, 0402")
      (fields (field (name "MANUFACTURER") "Vishay-Dale") (field (name "PARTNUMBER") "CRCW040249R9FKED"))
      (libsource (lib "Altium Vault - TI") (part "Resistor"))
    )
    (comp (ref "R6")
      (value "49.9")
      (footprint "0402")
      (description "RES, 49.9, 1%, 0.063 W, AEC-Q200 Grade 0, 0402")
      (fields (field (name "MANUFACTURER") "Vishay-Dale") (field (name "PARTNUMBER") "CRCW040249R9FKED"))
      (libsource (lib "Altium Vault - TI") (part "Resistor"))
    )
    (comp (ref "R7")
      (value "49.9")
      (footprint "0402")
      (description "RES, 49.9, 1%, 0.063 W, AEC-Q200 Grade 0, 0402")
      (fields (field (name "MANUFACTURER") "Vishay-Dale") (field (name "PARTNUMBER") "CRCW040249R9FKED"))
      (libsource (lib "Altium Vault - TI") (part "Resistor"))
    )
    (comp (ref "R8")
      (value "49.9")
      (footprint "0402")
      (description "RES, 49.9, 1%, 0.063 W, AEC-Q200 Grade 0, 0402")
      (fields (field (name "MANUFACTURER") "Vishay-Dale") (field (name "PARTNUMBER") "CRCW040249R9FKED"))
      (libsource (lib "Altium Vault - TI") (part "Resistor"))
    )
    (comp (ref "R9")
      (value "49.9")
      (footprint "0402")
      (description "RES, 49.9, 1%, 0.063 W, AEC-Q200 Grade 0, 0402")
      (fields (field (name "MANUFACTURER") "Vishay-Dale") (field (name "PARTNUMBER") "CRCW040249R9FKED"))
      (libsource (lib "Altium Vault - TI") (part "Resistor"))
    )
    (comp (ref "R10")
      (value "49.9")
      (footprint "0402")
      (description "RES, 49.9, 1%, 0.063 W, AEC-Q200 Grade 0, 0402")
      (fields (field (name "MANUFACTURER") "Vishay-Dale") (field (name "PARTNUMBER") "CRCW040249R9FKED"))
      (libsource (lib "Altium Vault - TI") (part "Resistor"))
    )
    (comp (ref "R11")
      (value "49.9")
      (footprint "0402")
      (description "RES, 49.9, 1%, 0.063 W, AEC-Q200 Grade 0, 0402")
      (fields (field (name "MANUFACTURER") "Vishay-Dale") (field (name "PARTNUMBER") "CRCW040249R9FKED"))
      (libsource (lib "Altium Vault - TI") (part "Resistor"))
    )
    (comp (ref "R12")
      (value "49.9")
      (footprint "0402")
      (description "RES, 49.9, 1%, 0.063 W, AEC-Q200 Grade 0, 0402")
      (fields (field (name "MANUFACTURER") "Vishay-Dale") (field (name "PARTNUMBER") "CRCW040249R9FKED"))
      (libsource (lib "Altium Vault - TI") (part "Resistor"))
    )
    (comp (ref "R13")
      (value "49.9")
      (footprint "0402")
      (description "RES, 49.9, 1%, 0.063 W, AEC-Q200 Grade 0, 0402")
      (fields (field (name "MANUFACTURER") "Vishay-Dale") (field (name "PARTNUMBER") "CRCW040249R9FKED"))
      (libsource (lib "Altium Vault - TI") (part "Resistor"))
    )
    (comp (ref "R14")
      (value "49.9")
      (footprint "0402")
      (description "RES, 49.9, 1%, 0.063 W, AEC-Q200 Grade 0, 0402")
      (fields (field (name "MANUFACTURER") "Vishay-Dale") (field (name "PARTNUMBER") "CRCW040249R9FKED"))
      (libsource (lib "Altium Vault - TI") (part "Resistor"))
    )
    (comp (ref "R15")
      (value "49.9")
      (footprint "0402")
      (description "RES, 49.9, 1%, 0.063 W, AEC-Q200 Grade 0, 0402")
      (fields (field (name "MANUFACTURER") "Vishay-Dale") (field (name "PARTNUMBER") "CRCW040249R9FKED"))
      (libsource (lib "Altium Vault - TI") (part "Resistor"))
    )
    (comp (ref "R16")
      (value "49.9")
      (footprint "0402")
      (description "RES, 49.9, 1%, 0.063 W, AEC-Q200 Grade 0, 0402")
      (fields (field (name "MANUFACTURER") "Vishay-Dale") (field (name "PARTNUMBER") "CRCW040249R9FKED"))
      (libsource (lib "Altium Vault - TI") (part "Resistor"))
    )
    (comp (ref "R17")
      (value "49.9")
      (footprint "0402")
      (description "RES, 49.9, 1%, 0.063 W, AEC-Q200 Grade 0, 0402")
      (fields (field (name "MANUFACTURER") "Vishay-Dale") (field (name "PARTNUMBER") "CRCW040249R9FKED"))
      (libsource (lib "Altium Vault - TI") (part "Resistor"))
    )
    (comp (ref "R18")
      (value "49.9")
      (footprint "0402")
      (description "RES, 49.9, 1%, 0.063 W, AEC-Q200 Grade 0, 0402")
      (fields (field (name "MANUFACTURER") "Vishay-Dale") (field (name "PARTNUMBER") "CRCW040249R9FKED"))
      (libsource (lib "Altium Vault - TI") (part "Resistor"))
    )
    (comp (ref "R19")
      (value "49.9")
      (footprint "0402")
      (description "RES, 49.9, 1%, 0.063 W, AEC-Q200 Grade 0, 0402")
      (fields (field (name "MANUFACTURER") "Vishay-Dale") (field (name "PARTNUMBER") "CRCW040249R9FKED"))
      (libsource (lib "Altium Vault - TI") (part "Resistor"))
    )
    (comp (ref "R20")
      (value "49.9")
      (footprint "0402")
      (description "RES, 49.9, 1%, 0.063 W, AEC-Q200 Grade 0, 0402")
      (fields (field (name "MANUFACTURER") "Vishay-Dale") (field (name "PARTNUMBER") "CRCW040249R9FKED"))
      (libsource (lib "Altium Vault - TI") (part "Resistor"))
    )
    (comp (ref "R21")
      (value "49.9")
      (footprint "0402")
      (description "RES, 49.9, 1%, 0.063 W, AEC-Q200 Grade 0, 0402")
      (fields (field (name "MANUFACTURER") "Vishay-Dale") (field (name "PARTNUMBER") "CRCW040249R9FKED"))
      (libsource (lib "Altium Vault - TI") (part "Resistor"))
    )
    (comp (ref "R22")
      (value "49.9")
      (footprint "0402")
      (description "RES, 49.9, 1%, 0.063 W, AEC-Q200 Grade 0, 0402")
      (fields (field (name "MANUFACTURER") "Vishay-Dale") (field (name "PARTNUMBER") "CRCW040249R9FKED"))
      (libsource (lib "Altium Vault - TI") (part "Resistor"))
    )
    (comp (ref "R23")
      (value "49.9")
      (footprint "0402")
      (description "RES, 49.9, 1%, 0.063 W, AEC-Q200 Grade 0, 0402")
      (fields (field (name "MANUFACTURER") "Vishay-Dale") (field (name "PARTNUMBER") "CRCW040249R9FKED"))
      (libsource (lib "Altium Vault - TI") (part "Resistor"))
    )
    (comp (ref "R24")
      (value "49.9")
      (footprint "0402")
      (description "RES, 49.9, 1%, 0.063 W, AEC-Q200 Grade 0, 0402")
      (fields (field (name "MANUFACTURER") "Vishay-Dale") (field (name "PARTNUMBER") "CRCW040249R9FKED"))
      (libsource (lib "Altium Vault - TI") (part "Resistor"))
    )
    (comp (ref "R25")
      (value "49.9")
      (footprint "0402")
      (description "RES, 49.9, 1%, 0.063 W, AEC-Q200 Grade 0, 0402")
      (fields (field (name "MANUFACTURER") "Vishay-Dale") (field (name "PARTNUMBER") "CRCW040249R9FKED"))
      (libsource (lib "Altium Vault - TI") (part "Resistor"))
    )
    (comp (ref "R26")
      (value "49.9")
      (footprint "0402")
      (description "RES, 49.9, 1%, 0.063 W, AEC-Q200 Grade 0, 0402")
      (fields (field (name "MANUFACTURER") "Vishay-Dale") (field (name "PARTNUMBER") "CRCW040249R9FKED"))
      (libsource (lib "Altium Vault - TI") (part "Resistor"))
    )
    (comp (ref "R27")
      (value "49.9")
      (footprint "0402")
      (description "RES, 49.9, 1%, 0.063 W, AEC-Q200 Grade 0, 0402")
      (fields (field (name "MANUFACTURER") "Vishay-Dale") (field (name "PARTNUMBER") "CRCW040249R9FKED"))
      (libsource (lib "Altium Vault - TI") (part "Resistor"))
    )
    (comp (ref "R28")
      (value "49.9")
      (footprint "0402")
      (description "RES, 49.9, 1%, 0.063 W, AEC-Q200 Grade 0, 0402")
      (fields (field (name "MANUFACTURER") "Vishay-Dale") (field (name "PARTNUMBER") "CRCW040249R9FKED"))
      (libsource (lib "Altium Vault - TI") (part "Resistor"))
    )
    (comp (ref "R29")
      (value "49.9")
      (footprint "0402")
      (description "RES, 49.9, 1%, 0.063 W, AEC-Q200 Grade 0, 0402")
      (fields (field (name "MANUFACTURER") "Vishay-Dale") (field (name "PARTNUMBER") "CRCW040249R9FKED"))
      (libsource (lib "Altium Vault - TI") (part "Resistor"))
    )
    (comp (ref "R30")
      (value "49.9")
      (footprint "0402")
      (description "RES, 49.9, 1%, 0.063 W, AEC-Q200 Grade 0, 0402")
      (fields (field (name "MANUFACTURER") "Vishay-Dale") (field (name "PARTNUMBER") "CRCW040249R9FKED"))
      (libsource (lib "Altium Vault - TI") (part "Resistor"))
    )
    (comp (ref "R31")
      (value "49.9")
      (footprint "0402")
      (description "RES, 49.9, 1%, 0.063 W, AEC-Q200 Grade 0, 0402")
      (fields (field (name "MANUFACTURER") "Vishay-Dale") (field (name "PARTNUMBER") "CRCW040249R9FKED"))
      (libsource (lib "Altium Vault - TI") (part "Resistor"))
    )
    (comp (ref "R32")
      (value "49.9")
      (footprint "0402")
      (description "RES, 49.9, 1%, 0.063 W, AEC-Q200 Grade 0, 0402")
      (fields (field (name "MANUFACTURER") "Vishay-Dale") (field (name "PARTNUMBER") "CRCW040249R9FKED"))
      (libsource (lib "Altium Vault - TI") (part "Resistor"))
    )
    (comp (ref "R33")
      (value "0")
      (footprint "0402")
      (description "RES, 0, 5%, 0.063 W, AEC-Q200 Grade 0, 0402")
      (fields (field (name "MANUFACTURER") "Vishay-Dale") (field (name "PARTNUMBER") "CRCW04020000Z0ED"))
      (libsource (lib "Altium Vault - TI") (part "Resistor"))
    )
    (comp (ref "R188")
      (value "Resistor")
      (footprint "0805_HV")
      (description "RES, 0, 5%, 0.125 W, 0805")
      (fields
        (field (name "PARTNUMBER") "MCR10EZPJ000")
        (field (name "VALUEDISPLAYED") "0")
        (field (name "MANUFACTURER") "Rohm")
        (field (name "PUBLISHER") "Texas Instruments")
      )
      (libsource (lib "Altium Vault - TI") (part "Resistor"))
    )
    (comp (ref "R189")
      (value "Resistor")
      (footprint "0805_HV")
      (description "RES, 0, 5%, 0.125 W, 0805")
      (fields
        (field (name "PARTNUMBER") "MCR10EZPJ000")
        (field (name "VALUEDISPLAYED") "0")
        (field (name "MANUFACTURER") "Rohm")
        (field (name "PUBLISHER") "Texas Instruments")
      )
      (libsource (lib "Altium Vault - TI") (part "Resistor"))
    )
    (comp (ref "T1")
      (value "MNC_ADT4-1WT+")
      (footprint "MNC_CD542")
      (description "RF Transformer, 50 ohm, 2 to 775 MHz, SMT")
      (fields
        (field (name "PARTNUMBER") "ADT4-1WT+")
        (field (name "MANUFACTURER") "Minicircuits")
        (field (name "PUBLISHER") "Texas Instruments")
      )
      (libsource (lib "Altium Vault - TI") (part "MNC_ADT4-1WT+"))
    )
    (comp (ref "TP1")
      (value "Testpoint_Gray")
      (footprint "Keystone_5019")
      (description "Test Point, Miniature, SMT")
      (fields
        (field (name "PARTNUMBER") "5019")
        (field (name "MANUFACTURER") "Keystone")
        (field (name "PUBLISHER") "Texas Instruments")
      )
      (libsource (lib "Altium Vault - TI") (part "Testpoint_Gray"))
    )
    (comp (ref "TP2")
      (value "Testpoint_Gray")
      (footprint "Keystone_5019")
      (description "Test Point, Miniature, SMT")
      (fields
        (field (name "PARTNUMBER") "5019")
        (field (name "MANUFACTURER") "Keystone")
        (field (name "PUBLISHER") "Texas Instruments")
      )
      (libsource (lib "Altium Vault - TI") (part "Testpoint_Gray"))
    )
    (comp (ref "TP3")
      (value "Testpoint_Gray")
      (footprint "Keystone_5019")
      (description "Test Point, Miniature, SMT")
      (fields
        (field (name "PARTNUMBER") "5019")
        (field (name "MANUFACTURER") "Keystone")
        (field (name "PUBLISHER") "Texas Instruments")
      )
      (libsource (lib "Altium Vault - TI") (part "Testpoint_Gray"))
    )
    (comp (ref "TP4")
      (value "Testpoint_Gray")
      (footprint "Keystone_5019")
      (description "Test Point, Miniature, SMT")
      (fields
        (field (name "PARTNUMBER") "5019")
        (field (name "MANUFACTURER") "Keystone")
        (field (name "PUBLISHER") "Texas Instruments")
      )
      (libsource (lib "Altium Vault - TI") (part "Testpoint_Gray"))
    )
    (comp (ref "TP5")
      (value "Testpoint_Gray")
      (footprint "Keystone_5019")
      (description "Test Point, Miniature, SMT")
      (fields
        (field (name "PARTNUMBER") "5019")
        (field (name "MANUFACTURER") "Keystone")
        (field (name "PUBLISHER") "Texas Instruments")
      )
      (libsource (lib "Altium Vault - TI") (part "Testpoint_Gray"))
    )
    (comp (ref "TP6")
      (value "Testpoint_Gray")
      (footprint "Keystone_5019")
      (description "Test Point, Miniature, SMT")
      (fields
        (field (name "PARTNUMBER") "5019")
        (field (name "MANUFACTURER") "Keystone")
        (field (name "PUBLISHER") "Texas Instruments")
      )
      (libsource (lib "Altium Vault - TI") (part "Testpoint_Gray"))
    )
    (comp (ref "TP7")
      (value "Testpoint_Gray")
      (footprint "Keystone_5019")
      (description "Test Point, Miniature, SMT")
      (fields
        (field (name "PARTNUMBER") "5019")
        (field (name "MANUFACTURER") "Keystone")
        (field (name "PUBLISHER") "Texas Instruments")
      )
      (libsource (lib "Altium Vault - TI") (part "Testpoint_Gray"))
    )
    (comp (ref "TP8")
      (value "Testpoint_Gray")
      (footprint "Keystone_5019")
      (description "Test Point, Miniature, SMT")
      (fields
        (field (name "PARTNUMBER") "5019")
        (field (name "MANUFACTURER") "Keystone")
        (field (name "PUBLISHER") "Texas Instruments")
      )
      (libsource (lib "Altium Vault - TI") (part "Testpoint_Gray"))
    )
    (comp (ref "TP9")
      (value "Testpoint_Gray")
      (footprint "Keystone_5019")
      (description "Test Point, Miniature, SMT")
      (fields
        (field (name "PARTNUMBER") "5019")
        (field (name "MANUFACTURER") "Keystone")
        (field (name "PUBLISHER") "Texas Instruments")
      )
      (libsource (lib "Altium Vault - TI") (part "Testpoint_Gray"))
    )
    (comp (ref "TP10")
      (value "Testpoint_Gray")
      (footprint "Keystone_5019")
      (description "Test Point, Miniature, SMT")
      (fields
        (field (name "PARTNUMBER") "5019")
        (field (name "MANUFACTURER") "Keystone")
        (field (name "PUBLISHER") "Texas Instruments")
      )
      (libsource (lib "Altium Vault - TI") (part "Testpoint_Gray"))
    )
    (comp (ref "TP11")
      (value "Testpoint_Gray")
      (footprint "Keystone_5019")
      (description "Test Point, Miniature, SMT")
      (fields
        (field (name "PARTNUMBER") "5019")
        (field (name "MANUFACTURER") "Keystone")
        (field (name "PUBLISHER") "Texas Instruments")
      )
      (libsource (lib "Altium Vault - TI") (part "Testpoint_Gray"))
    )
    (comp (ref "TP12")
      (value "Testpoint_Gray")
      (footprint "Keystone_5019")
      (description "Test Point, Miniature, SMT")
      (fields
        (field (name "PARTNUMBER") "5019")
        (field (name "MANUFACTURER") "Keystone")
        (field (name "PUBLISHER") "Texas Instruments")
      )
      (libsource (lib "Altium Vault - TI") (part "Testpoint_Gray"))
    )
    (comp (ref "TP13")
      (value "Testpoint_Gray")
      (footprint "Keystone_5019")
      (description "Test Point, Miniature, SMT")
      (fields
        (field (name "PARTNUMBER") "5019")
        (field (name "MANUFACTURER") "Keystone")
        (field (name "PUBLISHER") "Texas Instruments")
      )
      (libsource (lib "Altium Vault - TI") (part "Testpoint_Gray"))
    )
    (comp (ref "TP14")
      (value "Testpoint_Gray")
      (footprint "Keystone_5019")
      (description "Test Point, Miniature, SMT")
      (fields
        (field (name "PARTNUMBER") "5019")
        (field (name "MANUFACTURER") "Keystone")
        (field (name "PUBLISHER") "Texas Instruments")
      )
      (libsource (lib "Altium Vault - TI") (part "Testpoint_Gray"))
    )
    (comp (ref "TP15")
      (value "Testpoint_Gray")
      (footprint "Keystone_5019")
      (description "Test Point, Miniature, SMT")
      (fields
        (field (name "PARTNUMBER") "5019")
        (field (name "MANUFACTURER") "Keystone")
        (field (name "PUBLISHER") "Texas Instruments")
      )
      (libsource (lib "Altium Vault - TI") (part "Testpoint_Gray"))
    )
    (comp (ref "TP16")
      (value "Testpoint_Gray")
      (footprint "Keystone_5019")
      (description "Test Point, Miniature, SMT")
      (fields
        (field (name "PARTNUMBER") "5019")
        (field (name "MANUFACTURER") "Keystone")
        (field (name "PUBLISHER") "Texas Instruments")
      )
      (libsource (lib "Altium Vault - TI") (part "Testpoint_Gray"))
    )
    (comp (ref "TP17")
      (value "Testpoint_Gray")
      (footprint "Keystone_5019")
      (description "Test Point, Miniature, SMT")
      (fields
        (field (name "PARTNUMBER") "5019")
        (field (name "MANUFACTURER") "Keystone")
        (field (name "PUBLISHER") "Texas Instruments")
      )
      (libsource (lib "Altium Vault - TI") (part "Testpoint_Gray"))
    )
    (comp (ref "TP18")
      (value "Testpoint_Gray")
      (footprint "Keystone_5019")
      (description "Test Point, Miniature, SMT")
      (fields
        (field (name "PARTNUMBER") "5019")
        (field (name "MANUFACTURER") "Keystone")
        (field (name "PUBLISHER") "Texas Instruments")
      )
      (libsource (lib "Altium Vault - TI") (part "Testpoint_Gray"))
    )
    (comp (ref "TP19")
      (value "Testpoint_Gray")
      (footprint "Keystone_5019")
      (description "Test Point, Miniature, SMT")
      (fields
        (field (name "PARTNUMBER") "5019")
        (field (name "MANUFACTURER") "Keystone")
        (field (name "PUBLISHER") "Texas Instruments")
      )
      (libsource (lib "Altium Vault - TI") (part "Testpoint_Gray"))
    )
    (comp (ref "TP20")
      (value "Testpoint_Gray")
      (footprint "Keystone_5019")
      (description "Test Point, Miniature, SMT")
      (fields
        (field (name "PARTNUMBER") "5019")
        (field (name "MANUFACTURER") "Keystone")
        (field (name "PUBLISHER") "Texas Instruments")
      )
      (libsource (lib "Altium Vault - TI") (part "Testpoint_Gray"))
    )
    (comp (ref "TP21")
      (value "Testpoint_Gray")
      (footprint "Keystone_5019")
      (description "Test Point, Miniature, SMT")
      (fields
        (field (name "PARTNUMBER") "5019")
        (field (name "MANUFACTURER") "Keystone")
        (field (name "PUBLISHER") "Texas Instruments")
      )
      (libsource (lib "Altium Vault - TI") (part "Testpoint_Gray"))
    )
    (comp (ref "TP22")
      (value "Testpoint_Gray")
      (footprint "Keystone_5019")
      (description "Test Point, Miniature, SMT")
      (fields
        (field (name "PARTNUMBER") "5019")
        (field (name "MANUFACTURER") "Keystone")
        (field (name "PUBLISHER") "Texas Instruments")
      )
      (libsource (lib "Altium Vault - TI") (part "Testpoint_Gray"))
    )
    (comp (ref "TP23")
      (value "Testpoint_Gray")
      (footprint "Keystone_5019")
      (description "Test Point, Miniature, SMT")
      (fields
        (field (name "PARTNUMBER") "5019")
        (field (name "MANUFACTURER") "Keystone")
        (field (name "PUBLISHER") "Texas Instruments")
      )
      (libsource (lib "Altium Vault - TI") (part "Testpoint_Gray"))
    )
    (comp (ref "TP24")
      (value "Testpoint_Gray")
      (footprint "Keystone_5019")
      (description "Test Point, Miniature, SMT")
      (fields
        (field (name "PARTNUMBER") "5019")
        (field (name "MANUFACTURER") "Keystone")
        (field (name "PUBLISHER") "Texas Instruments")
      )
      (libsource (lib "Altium Vault - TI") (part "Testpoint_Gray"))
    )
    (comp (ref "TP25")
      (value "Testpoint_Gray")
      (footprint "Keystone_5019")
      (description "Test Point, Miniature, SMT")
      (fields
        (field (name "PARTNUMBER") "5019")
        (field (name "MANUFACTURER") "Keystone")
        (field (name "PUBLISHER") "Texas Instruments")
      )
      (libsource (lib "Altium Vault - TI") (part "Testpoint_Gray"))
    )
    (comp (ref "TP26")
      (value "Testpoint_Gray")
      (footprint "Keystone_5019")
      (description "Test Point, Miniature, SMT")
      (fields
        (field (name "PARTNUMBER") "5019")
        (field (name "MANUFACTURER") "Keystone")
        (field (name "PUBLISHER") "Texas Instruments")
      )
      (libsource (lib "Altium Vault - TI") (part "Testpoint_Gray"))
    )
    (comp (ref "TP27")
      (value "Testpoint_Gray")
      (footprint "Keystone_5019")
      (description "Test Point, Miniature, SMT")
      (fields
        (field (name "PARTNUMBER") "5019")
        (field (name "MANUFACTURER") "Keystone")
        (field (name "PUBLISHER") "Texas Instruments")
      )
      (libsource (lib "Altium Vault - TI") (part "Testpoint_Gray"))
    )
    (comp (ref "TP28")
      (value "Testpoint_Gray")
      (footprint "Keystone_5019")
      (description "Test Point, Miniature, SMT")
      (fields
        (field (name "PARTNUMBER") "5019")
        (field (name "MANUFACTURER") "Keystone")
        (field (name "PUBLISHER") "Texas Instruments")
      )
      (libsource (lib "Altium Vault - TI") (part "Testpoint_Gray"))
    )
    (comp (ref "TP29")
      (value "Testpoint_Gray")
      (footprint "Keystone_5019")
      (description "Test Point, Miniature, SMT")
      (fields
        (field (name "PARTNUMBER") "5019")
        (field (name "MANUFACTURER") "Keystone")
        (field (name "PUBLISHER") "Texas Instruments")
      )
      (libsource (lib "Altium Vault - TI") (part "Testpoint_Gray"))
    )
    (comp (ref "TP30")
      (value "Testpoint_Gray")
      (footprint "Keystone_5019")
      (description "Test Point, Miniature, SMT")
      (fields
        (field (name "PARTNUMBER") "5019")
        (field (name "MANUFACTURER") "Keystone")
        (field (name "PUBLISHER") "Texas Instruments")
      )
      (libsource (lib "Altium Vault - TI") (part "Testpoint_Gray"))
    )
    (comp (ref "TP31")
      (value "5001")
      (footprint "Keystone5001")
      (description "Test Point, Miniature, Black, TH")
      (fields (field (name "MANUFACTURER") "Keystone") (field (name "PUBLISHER") "Texas Instruments"))
      (libsource (lib "Altium Vault - TI") (part "5001"))
    )
    (comp (ref "TP32")
      (value "5001")
      (footprint "Keystone5001")
      (description "Test Point, Miniature, Black, TH")
      (fields (field (name "MANUFACTURER") "Keystone") (field (name "PUBLISHER") "Texas Instruments"))
      (libsource (lib "Altium Vault - TI") (part "5001"))
    )
    (comp (ref "TP33")
      (value "Testpoint_Gray")
      (footprint "Keystone_5019")
      (description "Test Point, Miniature, SMT")
      (fields
        (field (name "PARTNUMBER") "5019")
        (field (name "MANUFACTURER") "Keystone")
        (field (name "PUBLISHER") "Texas Instruments")
      )
      (libsource (lib "Altium Vault - TI") (part "Testpoint_Gray"))
    )
    (comp (ref "TP34")
      (value "Testpoint_Gray")
      (footprint "Keystone_5019")
      (description "Test Point, Miniature, SMT")
      (fields
        (field (name "PARTNUMBER") "5019")
        (field (name "MANUFACTURER") "Keystone")
        (field (name "PUBLISHER") "Texas Instruments")
      )
      (libsource (lib "Altium Vault - TI") (part "Testpoint_Gray"))
    )
  )
  (nets
    (net (code "1") (name "/CPLD_IO_2") (class "Default")
      (node (ref "T1") (pin "3") (pinfunction "3_3") (pintype "power_in"))
    )
    (net (code "2") (name "/INM1") (class "Default")
      (node (ref "C2") (pin "1") (pinfunction "1_1") (pintype "passive"))
    )
    (net (code "3") (name "/INM2") (class "Default")
      (node (ref "C4") (pin "1") (pinfunction "1_1") (pintype "passive"))
    )
    (net (code "4") (name "/INM3") (class "Default")
      (node (ref "C6") (pin "1") (pinfunction "1_1") (pintype "passive"))
    )
    (net (code "5") (name "/INM4") (class "Default")
      (node (ref "C8") (pin "1") (pinfunction "1_1") (pintype "passive"))
    )
    (net (code "6") (name "/INM5") (class "Default")
      (node (ref "C10") (pin "1") (pinfunction "1_1") (pintype "passive"))
    )
    (net (code "7") (name "/INM6") (class "Default")
      (node (ref "C11") (pin "1") (pinfunction "1_1") (pintype "passive"))
    )
    (net (code "8") (name "/INM7") (class "Default")
      (node (ref "C14") (pin "1") (pinfunction "1_1") (pintype "passive"))
    )
    (net (code "9") (name "/INM8") (class "Default")
      (node (ref "C15") (pin "1") (pinfunction "1_1") (pintype "passive"))
    )
    (net (code "10") (name "/INM9") (class "Default")
      (node (ref "C17") (pin "1") (pinfunction "1_1") (pintype "passive"))
    )
    (net (code "11") (name "/INM10") (class "Default")
      (node (ref "C20") (pin "1") (pinfunction "1_1") (pintype "passive"))
    )
    (net (code "12") (name "/INM11") (class "Default")
      (node (ref "C21") (pin "1") (pinfunction "1_1") (pintype "passive"))
    )
    (net (code "13") (name "/INM12") (class "Default")
      (node (ref "C24") (pin "1") (pinfunction "1_1") (pintype "passive"))
    )
    (net (code "14") (name "/INM13") (class "Default")
      (node (ref "C25") (pin "1") (pinfunction "1_1") (pintype "passive"))
    )
    (net (code "15") (name "/INM14") (class "Default")
      (node (ref "C28") (pin "1") (pinfunction "1_1") (pintype "passive"))
    )
    (net (code "16") (name "/INM15") (class "Default")
      (node (ref "C30") (pin "1") (pinfunction "1_1") (pintype "passive"))
    )
    (net (code "17") (name "/INM16") (class "Default")
      (node (ref "C32") (pin "1") (pinfunction "1_1") (pintype "passive"))
    )
    (net (code "18") (name "/INM17") (class "Default")
      (node (ref "C34") (pin "1") (pinfunction "1_1") (pintype "passive"))
    )
    (net (code "19") (name "/INM18") (class "Default")
      (node (ref "C36") (pin "1") (pinfunction "1_1") (pintype "passive"))
    )
    (net (code "20") (name "/INM19") (class "Default")
      (node (ref "C38") (pin "1") (pinfunction "1_1") (pintype "passive"))
    )
    (net (code "21") (name "/INM20") (class "Default")
      (node (ref "C40") (pin "1") (pinfunction "1_1") (pintype "passive"))
    )
    (net (code "22") (name "/INM21") (class "Default")
      (node (ref "C42") (pin "1") (pinfunction "1_1") (pintype "passive"))
    )
    (net (code "23") (name "/INM22") (class "Default")
      (node (ref "C44") (pin "1") (pinfunction "1_1") (pintype "passive"))
    )
    (net (code "24") (name "/INM23") (class "Default")
      (node (ref "C46") (pin "1") (pinfunction "1_1") (pintype "passive"))
    )
    (net (code "25") (name "/INM24") (class "Default")
      (node (ref "C48") (pin "1") (pinfunction "1_1") (pintype "passive"))
    )
    (net (code "26") (name "/INM25") (class "Default")
      (node (ref "C50") (pin "1") (pinfunction "1_1") (pintype "passive"))
    )
    (net (code "27") (name "/INM26") (class "Default")
      (node (ref "C52") (pin "1") (pinfunction "1_1") (pintype "passive"))
    )
    (net (code "28") (name "/INM27") (class "Default")
      (node (ref "C54") (pin "1") (pinfunction "1_1") (pintype "passive"))
    )
    (net (code "29") (name "/INM28") (class "Default")
      (node (ref "C56") (pin "1") (pinfunction "1_1") (pintype "passive"))
    )
    (net (code "30") (name "/INM29") (class "Default")
      (node (ref "C58") (pin "1") (pinfunction "1_1") (pintype "passive"))
    )
    (net (code "31") (name "/INM30") (class "Default")
      (node (ref "C59") (pin "1") (pinfunction "1_1") (pintype "passive"))
    )
    (net (code "32") (name "/INM31") (class "Default")
      (node (ref "C61") (pin "1") (pinfunction "1_1") (pintype "passive"))
    )
    (net (code "33") (name "/INM32") (class "Default")
      (node (ref "C63") (pin "1") (pinfunction "1_1") (pintype "passive"))
    )
    (net (code "35") (name "/INP1") (class "Default")
      (node (ref "C1") (pin "1") (pinfunction "1_1") (pintype "passive"))
    )
    (net (code "36") (name "/INP2") (class "Default")
      (node (ref "C3") (pin "1") (pinfunction "1_1") (pintype "passive"))
    )
    (net (code "37") (name "/INP3") (class "Default")
      (node (ref "C5") (pin "1") (pinfunction "1_1") (pintype "passive"))
    )
    (net (code "38") (name "/INP4") (class "Default")
      (node (ref "C7") (pin "1") (pinfunction "1_1") (pintype "passive"))
    )
    (net (code "39") (name "/INP5") (class "Default")
      (node (ref "C9") (pin "1") (pinfunction "1_1") (pintype "passive"))
    )
    (net (code "40") (name "/INP6") (class "Default")
      (node (ref "C12") (pin "1") (pinfunction "1_1") (pintype "passive"))
    )
    (net (code "41") (name "/INP7") (class "Default")
      (node (ref "C13") (pin "1") (pinfunction "1_1") (pintype "passive"))
    )
    (net (code "42") (name "/INP8") (class "Default")
      (node (ref "C16") (pin "1") (pinfunction "1_1") (pintype "passive"))
    )
    (net (code "43") (name "/INP9") (class "Default")
      (node (ref "C18") (pin "1") (pinfunction "1_1") (pintype "passive"))
    )
    (net (code "44") (name "/INP10") (class "Default")
      (node (ref "C19") (pin "1") (pinfunction "1_1") (pintype "passive"))
    )
    (net (code "45") (name "/INP11") (class "Default")
      (node (ref "C22") (pin "1") (pinfunction "1_1") (pintype "passive"))
    )
    (net (code "46") (name "/INP12") (class "Default")
      (node (ref "C23") (pin "1") (pinfunction "1_1") (pintype "passive"))
    )
    (net (code "47") (name "/INP13") (class "Default")
      (node (ref "C26") (pin "1") (pinfunction "1_1") (pintype "passive"))
    )
    (net (code "48") (name "/INP14") (class "Default")
      (node (ref "C27") (pin "1") (pinfunction "1_1") (pintype "passive"))
    )
    (net (code "49") (name "/INP15") (class "Default")
      (node (ref "C29") (pin "1") (pinfunction "1_1") (pintype "passive"))
    )
    (net (code "50") (name "/INP16") (class "Default")
      (node (ref "C31") (pin "1") (pinfunction "1_1") (pintype "passive"))
    )
    (net (code "51") (name "/INP17") (class "Default")
      (node (ref "C33") (pin "1") (pinfunction "1_1") (pintype "passive"))
    )
    (net (code "52") (name "/INP18") (class "Default")
      (node (ref "C35") (pin "1") (pinfunction "1_1") (pintype "passive"))
    )
    (net (code "53") (name "/INP19") (class "Default")
      (node (ref "C37") (pin "1") (pinfunction "1_1") (pintype "passive"))
    )
    (net (code "54") (name "/INP20") (class "Default")
      (node (ref "C39") (pin "1") (pinfunction "1_1") (pintype "passive"))
    )
    (net (code "55") (name "/INP21") (class "Default")
      (node (ref "C41") (pin "1") (pinfunction "1_1") (pintype "passive"))
    )
    (net (code "56") (name "/INP22") (class "Default")
      (node (ref "C43") (pin "1") (pinfunction "1_1") (pintype "passive"))
    )
    (net (code "57") (name "/INP23") (class "Default")
      (node (ref "C45") (pin "1") (pinfunction "1_1") (pintype "passive"))
    )
    (net (code "58") (name "/INP24") (class "Default")
      (node (ref "C47") (pin "1") (pinfunction "1_1") (pintype "passive"))
    )
    (net (code "59") (name "/INP25") (class "Default")
      (node (ref "C49") (pin "1") (pinfunction "1_1") (pintype "passive"))
    )
    (net (code "60") (name "/INP26") (class "Default")
      (node (ref "C51") (pin "1") (pinfunction "1_1") (pintype "passive"))
    )
    (net (code "61") (name "/INP27") (class "Default")
      (node (ref "C53") (pin "1") (pinfunction "1_1") (pintype "passive"))
    )
    (net (code "62") (name "/INP28") (class "Default")
      (node (ref "C55") (pin "1") (pinfunction "1_1") (pintype "passive"))
    )
    (net (code "63") (name "/INP29") (class "Default")
      (node (ref "C57") (pin "1") (pinfunction "1_1") (pintype "passive"))
    )
    (net (code "64") (name "/INP30") (class "Default")
      (node (ref "C60") (pin "1") (pinfunction "1_1") (pintype "passive"))
    )
    (net (code "65") (name "/INP31") (class "Default")
      (node (ref "C62") (pin "1") (pinfunction "1_1") (pintype "passive"))
    )
    (net (code "66") (name "/INP32") (class "Default")
      (node (ref "C64") (pin "1") (pinfunction "1_1") (pintype "passive"))
    )
    (net (code "68") (name "/SMA_INP1") (class "Default")
      (node (ref "C1") (pin "2") (pinfunction "2_2") (pintype "passive"))
      (node (ref "J1") (pin "1") (pinfunction "1_1") (pintype "passive"))
      (node (ref "J7") (pin "1") (pinfunction "1_1") (pintype "passive"))
      (node (ref "J7") (pin "3") (pinfunction "3_3") (pintype "passive"))
      (node (ref "R1") (pin "2") (pinfunction "2_2") (pintype "passive"))
      (node (ref "TP1") (pin "1") (pintype "passive"))
    )
    (net (code "69") (name "/SMA_INP2") (class "Default")
      (node (ref "C3") (pin "2") (pinfunction "2_2") (pintype "passive"))
      (node (ref "J3") (pin "1") (pinfunction "1_1") (pintype "passive"))
      (node (ref "J7") (pin "11") (pinfunction "11_11") (pintype "passive"))
      (node (ref "J7") (pin "9") (pinfunction "9_9") (pintype "passive"))
      (node (ref "R2") (pin "2") (pinfunction "2_2") (pintype "passive"))
      (node (ref "TP3") (pin "1") (pintype "passive"))
    )
    (net (code "70") (name "/SMA_INP3") (class "Default")
      (node (ref "C5") (pin "2") (pinfunction "2_2") (pintype "passive"))
      (node (ref "J5") (pin "1") (pinfunction "1_1") (pintype "passive"))
      (node (ref "J7") (pin "17") (pinfunction "17_17") (pintype "passive"))
      (node (ref "J7") (pin "19") (pinfunction "19_19") (pintype "passive"))
      (node (ref "R3") (pin "2") (pinfunction "2_2") (pintype "passive"))
      (node (ref "TP5") (pin "1") (pintype "passive"))
    )
    (net (code "71") (name "/SMA_INP4") (class "Default")
      (node (ref "C7") (pin "2") (pinfunction "2_2") (pintype "passive"))
      (node (ref "J7") (pin "25") (pinfunction "25_25") (pintype "passive"))
      (node (ref "J7") (pin "27") (pinfunction "27_27") (pintype "passive"))
      (node (ref "J8") (pin "1") (pinfunction "1_1") (pintype "passive"))
      (node (ref "R4") (pin "2") (pinfunction "2_2") (pintype "passive"))
      (node (ref "TP7") (pin "1") (pintype "passive"))
    )
    (net (code "72") (name "/SMA_INP5") (class "Default")
      (node (ref "C9") (pin "2") (pinfunction "2_2") (pintype "passive"))
      (node (ref "J10") (pin "1") (pinfunction "1_1") (pintype "passive"))
      (node (ref "J7") (pin "33") (pinfunction "33_33") (pintype "passive"))
      (node (ref "J7") (pin "35") (pinfunction "35_35") (pintype "passive"))
      (node (ref "R5") (pin "2") (pinfunction "2_2") (pintype "passive"))
      (node (ref "TP9") (pin "1") (pintype "passive"))
    )
    (net (code "73") (name "/SMA_INP6") (class "Default")
      (node (ref "C12") (pin "2") (pinfunction "2_2") (pintype "passive"))
      (node (ref "J12") (pin "1") (pinfunction "1_1") (pintype "passive"))
      (node (ref "J7") (pin "41") (pinfunction "41_41") (pintype "passive"))
      (node (ref "J7") (pin "43") (pinfunction "43_43") (pintype "passive"))
      (node (ref "R6") (pin "2") (pinfunction "2_2") (pintype "passive"))
      (node (ref "TP11") (pin "1") (pintype "passive"))
    )
    (net (code "74") (name "/SMA_INP7") (class "Default")
      (node (ref "C13") (pin "2") (pinfunction "2_2") (pintype "passive"))
      (node (ref "J14") (pin "1") (pinfunction "1_1") (pintype "passive"))
      (node (ref "J7") (pin "49") (pinfunction "49_49") (pintype "passive"))
      (node (ref "J7") (pin "51") (pinfunction "51_51") (pintype "passive"))
      (node (ref "R7") (pin "2") (pinfunction "2_2") (pintype "passive"))
      (node (ref "TP13") (pin "1") (pintype "passive"))
    )
    (net (code "75") (name "/SMA_INP8") (class "Default")
      (node (ref "C16") (pin "2") (pinfunction "2_2") (pintype "passive"))
      (node (ref "J16") (pin "1") (pinfunction "1_1") (pintype "passive"))
      (node (ref "J7") (pin "57") (pinfunction "57_57") (pintype "passive"))
      (node (ref "J7") (pin "59") (pinfunction "59_59") (pintype "passive"))
      (node (ref "R8") (pin "2") (pinfunction "2_2") (pintype "passive"))
      (node (ref "TP15") (pin "1") (pintype "passive"))
    )
    (net (code "76") (name "/SMA_INP9") (class "Default")
      (node (ref "C18") (pin "2") (pinfunction "2_2") (pintype "passive"))
      (node (ref "J19") (pin "1") (pinfunction "1_1") (pintype "passive"))
      (node (ref "J7") (pin "61") (pinfunction "61_61") (pintype "passive"))
      (node (ref "J7") (pin "63") (pinfunction "63_63") (pintype "passive"))
      (node (ref "R9") (pin "2") (pinfunction "2_2") (pintype "passive"))
      (node (ref "TP17") (pin "1") (pintype "passive"))
    )
    (net (code "77") (name "/SMA_INP10") (class "Default")
      (node (ref "C19") (pin "2") (pinfunction "2_2") (pintype "passive"))
      (node (ref "J21") (pin "1") (pinfunction "1_1") (pintype "passive"))
      (node (ref "J7") (pin "69") (pinfunction "69_69") (pintype "passive"))
      (node (ref "J7") (pin "71") (pinfunction "71_71") (pintype "passive"))
      (node (ref "R10") (pin "2") (pinfunction "2_2") (pintype "passive"))
      (node (ref "TP19") (pin "1") (pintype "passive"))
    )
    (net (code "78") (name "/SMA_INP11") (class "Default")
      (node (ref "C22") (pin "2") (pinfunction "2_2") (pintype "passive"))
      (node (ref "J23") (pin "1") (pinfunction "1_1") (pintype "passive"))
      (node (ref "J7") (pin "77") (pinfunction "77_77") (pintype "passive"))
      (node (ref "J7") (pin "79") (pinfunction "79_79") (pintype "passive"))
      (node (ref "R11") (pin "2") (pinfunction "2_2") (pintype "passive"))
      (node (ref "TP21") (pin "1") (pintype "passive"))
    )
    (net (code "79") (name "/SMA_INP12") (class "Default")
      (node (ref "C23") (pin "2") (pinfunction "2_2") (pintype "passive"))
      (node (ref "J25") (pin "1") (pinfunction "1_1") (pintype "passive"))
      (node (ref "J7") (pin "85") (pinfunction "85_85") (pintype "passive"))
      (node (ref "J7") (pin "87") (pinfunction "87_87") (pintype "passive"))
      (node (ref "R12") (pin "2") (pinfunction "2_2") (pintype "passive"))
      (node (ref "TP23") (pin "1") (pintype "passive"))
    )
    (net (code "80") (name "/SMA_INP13") (class "Default")
      (node (ref "C26") (pin "2") (pinfunction "2_2") (pintype "passive"))
      (node (ref "J27") (pin "1") (pinfunction "1_1") (pintype "passive"))
      (node (ref "J7") (pin "93") (pinfunction "93_93") (pintype "passive"))
      (node (ref "J7") (pin "95") (pinfunction "95_95") (pintype "passive"))
      (node (ref "R13") (pin "2") (pinfunction "2_2") (pintype "passive"))
      (node (ref "TP25") (pin "1") (pintype "passive"))
    )
    (net (code "81") (name "/SMA_INP14") (class "Default")
      (node (ref "C27") (pin "2") (pinfunction "2_2") (pintype "passive"))
      (node (ref "J29") (pin "1") (pinfunction "1_1") (pintype "passive"))
      (node (ref "J7") (pin "101") (pinfunction "101_101") (pintype "passive"))
      (node (ref "J7") (pin "103") (pinfunction "103_103") (pintype "passive"))
      (node (ref "R14") (pin "2") (pinfunction "2_2") (pintype "passive"))
      (node (ref "TP27") (pin "1") (pintype "passive"))
    )
    (net (code "82") (name "/SMA_INP15") (class "Default")
      (node (ref "C29") (pin "2") (pinfunction "2_2") (pintype "passive"))
      (node (ref "J31") (pin "1") (pinfunction "1_1") (pintype "passive"))
      (node (ref "J7") (pin "109") (pinfunction "109_109") (pintype "passive"))
      (node (ref "J7") (pin "111") (pinfunction "111_111") (pintype "passive"))
      (node (ref "R15") (pin "2") (pinfunction "2_2") (pintype "passive"))
      (node (ref "TP29") (pin "1") (pintype "passive"))
    )
    (net (code "83") (name "/SMA_INP16") (class "Default")
      (node (ref "C31") (pin "2") (pinfunction "2_2") (pintype "passive"))
      (node (ref "J33") (pin "1") (pinfunction "1_1") (pintype "passive"))
      (node (ref "J7") (pin "117") (pinfunction "117_117") (pintype "passive"))
      (node (ref "J7") (pin "119") (pinfunction "119_119") (pintype "passive"))
      (node (ref "R16") (pin "2") (pinfunction "2_2") (pintype "passive"))
      (node (ref "TP33") (pin "1") (pintype "passive"))
    )
    (net (code "84") (name "/SMA_INP17") (class "Default")
      (node (ref "C33") (pin "2") (pinfunction "2_2") (pintype "passive"))
      (node (ref "J18") (pin "1") (pinfunction "1_1") (pintype "passive"))
      (node (ref "J18") (pin "3") (pinfunction "3_3") (pintype "passive"))
      (node (ref "J2") (pin "1") (pinfunction "1_1") (pintype "passive"))
      (node (ref "R17") (pin "2") (pinfunction "2_2") (pintype "passive"))
      (node (ref "TP2") (pin "1") (pintype "passive"))
    )
    (net (code "85") (name "/SMA_INP18") (class "Default")
      (node (ref "C35") (pin "2") (pinfunction "2_2") (pintype "passive"))
      (node (ref "J18") (pin "11") (pinfunction "11_11") (pintype "passive"))
      (node (ref "J18") (pin "9") (pinfunction "9_9") (pintype "passive"))
      (node (ref "J4") (pin "1") (pinfunction "1_1") (pintype "passive"))
      (node (ref "R18") (pin "2") (pinfunction "2_2") (pintype "passive"))
      (node (ref "TP4") (pin "1") (pintype "passive"))
    )
    (net (code "86") (name "/SMA_INP19") (class "Default")
      (node (ref "C37") (pin "2") (pinfunction "2_2") (pintype "passive"))
      (node (ref "J18") (pin "17") (pinfunction "17_17") (pintype "passive"))
      (node (ref "J18") (pin "19") (pinfunction "19_19") (pintype "passive"))
      (node (ref "J6") (pin "1") (pinfunction "1_1") (pintype "passive"))
      (node (ref "R19") (pin "2") (pinfunction "2_2") (pintype "passive"))
      (node (ref "TP6") (pin "1") (pintype "passive"))
    )
    (net (code "87") (name "/SMA_INP20") (class "Default")
      (node (ref "C39") (pin "2") (pinfunction "2_2") (pintype "passive"))
      (node (ref "J18") (pin "25") (pinfunction "25_25") (pintype "passive"))
      (node (ref "J18") (pin "27") (pinfunction "27_27") (pintype "passive"))
      (node (ref "J9") (pin "1") (pinfunction "1_1") (pintype "passive"))
      (node (ref "R20") (pin "2") (pinfunction "2_2") (pintype "passive"))
      (node (ref "TP8") (pin "1") (pintype "passive"))
    )
    (net (code "88") (name "/SMA_INP21") (class "Default")
      (node (ref "C41") (pin "2") (pinfunction "2_2") (pintype "passive"))
      (node (ref "J11") (pin "1") (pinfunction "1_1") (pintype "passive"))
      (node (ref "J18") (pin "33") (pinfunction "33_33") (pintype "passive"))
      (node (ref "J18") (pin "35") (pinfunction "35_35") (pintype "passive"))
      (node (ref "R21") (pin "2") (pinfunction "2_2") (pintype "passive"))
      (node (ref "TP10") (pin "1") (pintype "passive"))
    )
    (net (code "89") (name "/SMA_INP22") (class "Default")
      (node (ref "C43") (pin "2") (pinfunction "2_2") (pintype "passive"))
      (node (ref "J13") (pin "1") (pinfunction "1_1") (pintype "passive"))
      (node (ref "J18") (pin "41") (pinfunction "41_41") (pintype "passive"))
      (node (ref "J18") (pin "43") (pinfunction "43_43") (pintype "passive"))
      (node (ref "R22") (pin "2") (pinfunction "2_2") (pintype "passive"))
      (node (ref "TP12") (pin "1") (pintype "passive"))
    )
    (net (code "90") (name "/SMA_INP23") (class "Default")
      (node (ref "C45") (pin "2") (pinfunction "2_2") (pintype "passive"))
      (node (ref "J15") (pin "1") (pinfunction "1_1") (pintype "passive"))
      (node (ref "J18") (pin "49") (pinfunction "49_49") (pintype "passive"))
      (node (ref "J18") (pin "51") (pinfunction "51_51") (pintype "passive"))
      (node (ref "R23") (pin "2") (pinfunction "2_2") (pintype "passive"))
      (node (ref "TP14") (pin "1") (pintype "passive"))
    )
    (net (code "91") (name "/SMA_INP24") (class "Default")
      (node (ref "C47") (pin "2") (pinfunction "2_2") (pintype "passive"))
      (node (ref "J17") (pin "1") (pinfunction "1_1") (pintype "passive"))
      (node (ref "J18") (pin "57") (pinfunction "57_57") (pintype "passive"))
      (node (ref "J18") (pin "59") (pinfunction "59_59") (pintype "passive"))
      (node (ref "R24") (pin "2") (pinfunction "2_2") (pintype "passive"))
      (node (ref "TP16") (pin "1") (pintype "passive"))
    )
    (net (code "92") (name "/SMA_INP25") (class "Default")
      (node (ref "C49") (pin "2") (pinfunction "2_2") (pintype "passive"))
      (node (ref "J18") (pin "61") (pinfunction "61_61") (pintype "passive"))
      (node (ref "J18") (pin "63") (pinfunction "63_63") (pintype "passive"))
      (node (ref "J20") (pin "1") (pinfunction "1_1") (pintype "passive"))
      (node (ref "R25") (pin "2") (pinfunction "2_2") (pintype "passive"))
      (node (ref "TP18") (pin "1") (pintype "passive"))
    )
    (net (code "93") (name "/SMA_INP26") (class "Default")
      (node (ref "C51") (pin "2") (pinfunction "2_2") (pintype "passive"))
      (node (ref "J18") (pin "69") (pinfunction "69_69") (pintype "passive"))
      (node (ref "J18") (pin "71") (pinfunction "71_71") (pintype "passive"))
      (node (ref "J22") (pin "1") (pinfunction "1_1") (pintype "passive"))
      (node (ref "R26") (pin "2") (pinfunction "2_2") (pintype "passive"))
      (node (ref "TP20") (pin "1") (pintype "passive"))
    )
    (net (code "94") (name "/SMA_INP27") (class "Default")
      (node (ref "C53") (pin "2") (pinfunction "2_2") (pintype "passive"))
      (node (ref "J18") (pin "77") (pinfunction "77_77") (pintype "passive"))
      (node (ref "J18") (pin "79") (pinfunction "79_79") (pintype "passive"))
      (node (ref "J24") (pin "1") (pinfunction "1_1") (pintype "passive"))
      (node (ref "R27") (pin "2") (pinfunction "2_2") (pintype "passive"))
      (node (ref "TP22") (pin "1") (pintype "passive"))
    )
    (net (code "95") (name "/SMA_INP28") (class "Default")
      (node (ref "C55") (pin "2") (pinfunction "2_2") (pintype "passive"))
      (node (ref "J18") (pin "85") (pinfunction "85_85") (pintype "passive"))
      (node (ref "J18") (pin "87") (pinfunction "87_87") (pintype "passive"))
      (node (ref "J26") (pin "1") (pinfunction "1_1") (pintype "passive"))
      (node (ref "R28") (pin "2") (pinfunction "2_2") (pintype "passive"))
      (node (ref "TP24") (pin "1") (pintype "passive"))
    )
    (net (code "96") (name "/SMA_INP29") (class "Default")
      (node (ref "C57") (pin "2") (pinfunction "2_2") (pintype "passive"))
      (node (ref "J18") (pin "93") (pinfunction "93_93") (pintype "passive"))
      (node (ref "J18") (pin "95") (pinfunction "95_95") (pintype "passive"))
      (node (ref "J28") (pin "1") (pinfunction "1_1") (pintype "passive"))
      (node (ref "R29") (pin "2") (pinfunction "2_2") (pintype "passive"))
      (node (ref "TP26") (pin "1") (pintype "passive"))
    )
    (net (code "97") (name "/SMA_INP30") (class "Default")
      (node (ref "C60") (pin "2") (pinfunction "2_2") (pintype "passive"))
      (node (ref "J18") (pin "101") (pinfunction "101_101") (pintype "passive"))
      (node (ref "J18") (pin "103") (pinfunction "103_103") (pintype "passive"))
      (node (ref "J30") (pin "1") (pinfunction "1_1") (pintype "passive"))
      (node (ref "R30") (pin "2") (pinfunction "2_2") (pintype "passive"))
      (node (ref "TP28") (pin "1") (pintype "passive"))
    )
    (net (code "98") (name "/SMA_INP31") (class "Default")
      (node (ref "C62") (pin "2") (pinfunction "2_2") (pintype "passive"))
      (node (ref "J18") (pin "109") (pinfunction "109_109") (pintype "passive"))
      (node (ref "J18") (pin "111") (pinfunction "111_111") (pintype "passive"))
      (node (ref "J32") (pin "1") (pinfunction "1_1") (pintype "passive"))
      (node (ref "R31") (pin "2") (pinfunction "2_2") (pintype "passive"))
      (node (ref "TP30") (pin "1") (pintype "passive"))
    )
    (net (code "99") (name "/SMA_INP32") (class "Default")
      (node (ref "C64") (pin "2") (pinfunction "2_2") (pintype "passive"))
      (node (ref "J18") (pin "117") (pinfunction "117_117") (pintype "passive"))
      (node (ref "J18") (pin "119") (pinfunction "119_119") (pintype "passive"))
      (node (ref "J34") (pin "1") (pinfunction "1_1") (pintype "passive"))
      (node (ref "R32") (pin "2") (pinfunction "2_2") (pintype "passive"))
      (node (ref "R33") (pin "2") (pinfunction "2_2") (pintype "passive"))
      (node (ref "TP34") (pin "1") (pintype "passive"))
    )
    (net (code "100") (name "AGND") (class "Default")
      (node (ref "C10") (pin "2") (pinfunction "2_2") (pintype "passive"))
      (node (ref "C11") (pin "2") (pinfunction "2_2") (pintype "passive"))
      (node (ref "C14") (pin "2") (pinfunction "2_2") (pintype "passive"))
      (node (ref "C15") (pin "2") (pinfunction "2_2") (pintype "passive"))
      (node (ref "C17") (pin "2") (pinfunction "2_2") (pintype "passive"))
      (node (ref "C2") (pin "2") (pinfunction "2_2") (pintype "passive"))
      (node (ref "C20") (pin "2") (pinfunction "2_2") (pintype "passive"))
      (node (ref "C21") (pin "2") (pinfunction "2_2") (pintype "passive"))
      (node (ref "C24") (pin "2") (pinfunction "2_2") (pintype "passive"))
      (node (ref "C25") (pin "2") (pinfunction "2_2") (pintype "passive"))
      (node (ref "C28") (pin "2") (pinfunction "2_2") (pintype "passive"))
      (node (ref "C30") (pin "2") (pinfunction "2_2") (pintype "passive"))
      (node (ref "C32") (pin "2") (pinfunction "2_2") (pintype "passive"))
      (node (ref "C34") (pin "2") (pinfunction "2_2") (pintype "passive"))
      (node (ref "C36") (pin "2") (pinfunction "2_2") (pintype "passive"))
      (node (ref "C38") (pin "2") (pinfunction "2_2") (pintype "passive"))
      (node (ref "C4") (pin "2") (pinfunction "2_2") (pintype "passive"))
      (node (ref "C40") (pin "2") (pinfunction "2_2") (pintype "passive"))
      (node (ref "C42") (pin "2") (pinfunction "2_2") (pintype "passive"))
      (node (ref "C44") (pin "2") (pinfunction "2_2") (pintype "passive"))
      (node (ref "C46") (pin "2") (pinfunction "2_2") (pintype "passive"))
      (node (ref "C48") (pin "2") (pinfunction "2_2") (pintype "passive"))
      (node (ref "C50") (pin "2") (pinfunction "2_2") (pintype "passive"))
      (node (ref "C52") (pin "2") (pinfunction "2_2") (pintype "passive"))
      (node (ref "C54") (pin "2") (pinfunction "2_2") (pintype "passive"))
      (node (ref "C56") (pin "2") (pinfunction "2_2") (pintype "passive"))
      (node (ref "C58") (pin "2") (pinfunction "2_2") (pintype "passive"))
      (node (ref "C59") (pin "2") (pinfunction "2_2") (pintype "passive"))
      (node (ref "C6") (pin "2") (pinfunction "2_2") (pintype "passive"))
      (node (ref "C61") (pin "2") (pinfunction "2_2") (pintype "passive"))
      (node (ref "C63") (pin "2") (pinfunction "2_2") (pintype "passive"))
      (node (ref "C8") (pin "2") (pinfunction "2_2") (pintype "passive"))
      (node (ref "J1") (pin "2") (pinfunction "2_2") (pintype "passive"))
      (node (ref "J1") (pin "3") (pinfunction "3_3") (pintype "passive"))
      (node (ref "J1") (pin "4") (pinfunction "4_4") (pintype "passive"))
      (node (ref "J1") (pin "5") (pinfunction "5_5") (pintype "passive"))
      (node (ref "J10") (pin "2") (pinfunction "2_2") (pintype "passive"))
      (node (ref "J10") (pin "3") (pinfunction "3_3") (pintype "passive"))
      (node (ref "J10") (pin "4") (pinfunction "4_4") (pintype "passive"))
      (node (ref "J10") (pin "5") (pinfunction "5_5") (pintype "passive"))
      (node (ref "J11") (pin "2") (pinfunction "2_2") (pintype "passive"))
      (node (ref "J11") (pin "3") (pinfunction "3_3") (pintype "passive"))
      (node (ref "J11") (pin "4") (pinfunction "4_4") (pintype "passive"))
      (node (ref "J11") (pin "5") (pinfunction "5_5") (pintype "passive"))
      (node (ref "J12") (pin "2") (pinfunction "2_2") (pintype "passive"))
      (node (ref "J12") (pin "3") (pinfunction "3_3") (pintype "passive"))
      (node (ref "J12") (pin "4") (pinfunction "4_4") (pintype "passive"))
      (node (ref "J12") (pin "5") (pinfunction "5_5") (pintype "passive"))
      (node (ref "J13") (pin "2") (pinfunction "2_2") (pintype "passive"))
      (node (ref "J13") (pin "3") (pinfunction "3_3") (pintype "passive"))
      (node (ref "J13") (pin "4") (pinfunction "4_4") (pintype "passive"))
      (node (ref "J13") (pin "5") (pinfunction "5_5") (pintype "passive"))
      (node (ref "J14") (pin "2") (pinfunction "2_2") (pintype "passive"))
      (node (ref "J14") (pin "3") (pinfunction "3_3") (pintype "passive"))
      (node (ref "J14") (pin "4") (pinfunction "4_4") (pintype "passive"))
      (node (ref "J14") (pin "5") (pinfunction "5_5") (pintype "passive"))
      (node (ref "J15") (pin "2") (pinfunction "2_2") (pintype "passive"))
      (node (ref "J15") (pin "3") (pinfunction "3_3") (pintype "passive"))
      (node (ref "J15") (pin "4") (pinfunction "4_4") (pintype "passive"))
      (node (ref "J15") (pin "5") (pinfunction "5_5") (pintype "passive"))
      (node (ref "J16") (pin "2") (pinfunction "2_2") (pintype "passive"))
      (node (ref "J16") (pin "3") (pinfunction "3_3") (pintype "passive"))
      (node (ref "J16") (pin "4") (pinfunction "4_4") (pintype "passive"))
      (node (ref "J16") (pin "5") (pinfunction "5_5") (pintype "passive"))
      (node (ref "J17") (pin "2") (pinfunction "2_2") (pintype "passive"))
      (node (ref "J17") (pin "3") (pinfunction "3_3") (pintype "passive"))
      (node (ref "J17") (pin "4") (pinfunction "4_4") (pintype "passive"))
      (node (ref "J17") (pin "5") (pinfunction "5_5") (pintype "passive"))
      (node (ref "J18") (pin "10") (pinfunction "10_10") (pintype "passive"))
      (node (ref "J18") (pin "100") (pinfunction "100_100") (pintype "passive"))
      (node (ref "J18") (pin "102") (pinfunction "102_102") (pintype "passive"))
      (node (ref "J18") (pin "104") (pinfunction "104_104") (pintype "passive"))
      (node (ref "J18") (pin "105") (pinfunction "105_105") (pintype "passive"))
      (node (ref "J18") (pin "106") (pinfunction "106_106") (pintype "passive"))
      (node (ref "J18") (pin "107") (pinfunction "107_107") (pintype "passive"))
      (node (ref "J18") (pin "108") (pinfunction "108_108") (pintype "passive"))
      (node (ref "J18") (pin "110") (pinfunction "110_110") (pintype "passive"))
      (node (ref "J18") (pin "112") (pinfunction "112_112") (pintype "passive"))
      (node (ref "J18") (pin "113") (pinfunction "113_113") (pintype "passive"))
      (node (ref "J18") (pin "114") (pinfunction "114_114") (pintype "passive"))
      (node (ref "J18") (pin "115") (pinfunction "115_115") (pintype "passive"))
      (node (ref "J18") (pin "116") (pinfunction "116_116") (pintype "passive"))
      (node (ref "J18") (pin "118") (pinfunction "118_118") (pintype "passive"))
      (node (ref "J18") (pin "12") (pinfunction "12_12") (pintype "passive"))
      (node (ref "J18") (pin "120") (pinfunction "120_120") (pintype "passive"))
      (node (ref "J18") (pin "13") (pinfunction "13_13") (pintype "passive"))
      (node (ref "J18") (pin "14") (pinfunction "14_14") (pintype "passive"))
      (node (ref "J18") (pin "15") (pinfunction "15_15") (pintype "passive"))
      (node (ref "J18") (pin "16") (pinfunction "16_16") (pintype "passive"))
      (node (ref "J18") (pin "18") (pinfunction "18_18") (pintype "passive"))
      (node (ref "J18") (pin "2") (pinfunction "2_2") (pintype "passive"))
      (node (ref "J18") (pin "20") (pinfunction "20_20") (pintype "passive"))
      (node (ref "J18") (pin "21") (pinfunction "21_21") (pintype "passive"))
      (node (ref "J18") (pin "22") (pinfunction "22_22") (pintype "passive"))
      (node (ref "J18") (pin "23") (pinfunction "23_23") (pintype "passive"))
      (node (ref "J18") (pin "24") (pinfunction "24_24") (pintype "passive"))
      (node (ref "J18") (pin "26") (pinfunction "26_26") (pintype "passive"))
      (node (ref "J18") (pin "28") (pinfunction "28_28") (pintype "passive"))
      (node (ref "J18") (pin "29") (pinfunction "29_29") (pintype "passive"))
      (node (ref "J18") (pin "30") (pinfunction "30_30") (pintype "passive"))
      (node (ref "J18") (pin "31") (pinfunction "31_31") (pintype "passive"))
      (node (ref "J18") (pin "32") (pinfunction "32_32") (pintype "passive"))
      (node (ref "J18") (pin "34") (pinfunction "34_34") (pintype "passive"))
      (node (ref "J18") (pin "36") (pinfunction "36_36") (pintype "passive"))
      (node (ref "J18") (pin "37") (pinfunction "37_37") (pintype "passive"))
      (node (ref "J18") (pin "38") (pinfunction "38_38") (pintype "passive"))
      (node (ref "J18") (pin "39") (pinfunction "39_39") (pintype "passive"))
      (node (ref "J18") (pin "4") (pinfunction "4_4") (pintype "passive"))
      (node (ref "J18") (pin "40") (pinfunction "40_40") (pintype "passive"))
      (node (ref "J18") (pin "42") (pinfunction "42_42") (pintype "passive"))
      (node (ref "J18") (pin "44") (pinfunction "44_44") (pintype "passive"))
      (node (ref "J18") (pin "45") (pinfunction "45_45") (pintype "passive"))
      (node (ref "J18") (pin "46") (pinfunction "46_46") (pintype "passive"))
      (node (ref "J18") (pin "47") (pinfunction "47_47") (pintype "passive"))
      (node (ref "J18") (pin "48") (pinfunction "48_48") (pintype "passive"))
      (node (ref "J18") (pin "5") (pinfunction "5_5") (pintype "passive"))
      (node (ref "J18") (pin "50") (pinfunction "50_50") (pintype "passive"))
      (node (ref "J18") (pin "52") (pinfunction "52_52") (pintype "passive"))
      (node (ref "J18") (pin "53") (pinfunction "53_53") (pintype "passive"))
      (node (ref "J18") (pin "54") (pinfunction "54_54") (pintype "passive"))
      (node (ref "J18") (pin "55") (pinfunction "55_55") (pintype "passive"))
      (node (ref "J18") (pin "56") (pinfunction "56_56") (pintype "passive"))
      (node (ref "J18") (pin "58") (pinfunction "58_58") (pintype "passive"))
      (node (ref "J18") (pin "6") (pinfunction "6_6") (pintype "passive"))
      (node (ref "J18") (pin "60") (pinfunction "60_60") (pintype "passive"))
      (node (ref "J18") (pin "62") (pinfunction "62_62") (pintype "passive"))
      (node (ref "J18") (pin "64") (pinfunction "64_64") (pintype "passive"))
      (node (ref "J18") (pin "65") (pinfunction "65_65") (pintype "passive"))
      (node (ref "J18") (pin "66") (pinfunction "66_66") (pintype "passive"))
      (node (ref "J18") (pin "67") (pinfunction "67_67") (pintype "passive"))
      (node (ref "J18") (pin "68") (pinfunction "68_68") (pintype "passive"))
      (node (ref "J18") (pin "7") (pinfunction "7_7") (pintype "passive"))
      (node (ref "J18") (pin "70") (pinfunction "70_70") (pintype "passive"))
      (node (ref "J18") (pin "72") (pinfunction "72_72") (pintype "passive"))
      (node (ref "J18") (pin "73") (pinfunction "73_73") (pintype "passive"))
      (node (ref "J18") (pin "74") (pinfunction "74_74") (pintype "passive"))
      (node (ref "J18") (pin "75") (pinfunction "75_75") (pintype "passive"))
      (node (ref "J18") (pin "76") (pinfunction "76_76") (pintype "passive"))
      (node (ref "J18") (pin "78") (pinfunction "78_78") (pintype "passive"))
      (node (ref "J18") (pin "8") (pinfunction "8_8") (pintype "passive"))
      (node (ref "J18") (pin "80") (pinfunction "80_80") (pintype "passive"))
      (node (ref "J18") (pin "81") (pinfunction "81_81") (pintype "passive"))
      (node (ref "J18") (pin "82") (pinfunction "82_82") (pintype "passive"))
      (node (ref "J18") (pin "83") (pinfunction "83_83") (pintype "passive"))
      (node (ref "J18") (pin "84") (pinfunction "84_84") (pintype "passive"))
      (node (ref "J18") (pin "86") (pinfunction "86_86") (pintype "passive"))
      (node (ref "J18") (pin "88") (pinfunction "88_88") (pintype "passive"))
      (node (ref "J18") (pin "89") (pinfunction "89_89") (pintype "passive"))
      (node (ref "J18") (pin "90") (pinfunction "90_90") (pintype "passive"))
      (node (ref "J18") (pin "91") (pinfunction "91_91") (pintype "passive"))
      (node (ref "J18") (pin "92") (pinfunction "92_92") (pintype "passive"))
      (node (ref "J18") (pin "94") (pinfunction "94_94") (pintype "passive"))
      (node (ref "J18") (pin "96") (pinfunction "96_96") (pintype "passive"))
      (node (ref "J18") (pin "97") (pinfunction "97_97") (pintype "passive"))
      (node (ref "J18") (pin "98") (pinfunction "98_98") (pintype "passive"))
      (node (ref "J18") (pin "99") (pinfunction "99_99") (pintype "passive"))
      (node (ref "J18") (pin "A1") (pinfunction "A1_A1") (pintype "power_in"))
      (node (ref "J18") (pin "A2") (pinfunction "A2_A2") (pintype "power_in"))
      (node (ref "J18") (pin "A3") (pinfunction "A3_A3") (pintype "power_in"))
      (node (ref "J18") (pin "A4") (pinfunction "A4_A4") (pintype "power_in"))
      (node (ref "J18") (pin "A5") (pinfunction "A5_A5") (pintype "power_in"))
      (node (ref "J18") (pin "A6") (pinfunction "A6_A6") (pintype "power_in"))
      (node (ref "J18") (pin "A7") (pinfunction "A7_A7") (pintype "power_in"))
      (node (ref "J18") (pin "A8") (pinfunction "A8_A8") (pintype "power_in"))
      (node (ref "J19") (pin "2") (pinfunction "2_2") (pintype "passive"))
      (node (ref "J19") (pin "3") (pinfunction "3_3") (pintype "passive"))
      (node (ref "J19") (pin "4") (pinfunction "4_4") (pintype "passive"))
      (node (ref "J19") (pin "5") (pinfunction "5_5") (pintype "passive"))
      (node (ref "J2") (pin "2") (pinfunction "2_2") (pintype "passive"))
      (node (ref "J2") (pin "3") (pinfunction "3_3") (pintype "passive"))
      (node (ref "J2") (pin "4") (pinfunction "4_4") (pintype "passive"))
      (node (ref "J2") (pin "5") (pinfunction "5_5") (pintype "passive"))
      (node (ref "J20") (pin "2") (pinfunction "2_2") (pintype "passive"))
      (node (ref "J20") (pin "3") (pinfunction "3_3") (pintype "passive"))
      (node (ref "J20") (pin "4") (pinfunction "4_4") (pintype "passive"))
      (node (ref "J20") (pin "5") (pinfunction "5_5") (pintype "passive"))
      (node (ref "J21") (pin "2") (pinfunction "2_2") (pintype "passive"))
      (node (ref "J21") (pin "3") (pinfunction "3_3") (pintype "passive"))
      (node (ref "J21") (pin "4") (pinfunction "4_4") (pintype "passive"))
      (node (ref "J21") (pin "5") (pinfunction "5_5") (pintype "passive"))
      (node (ref "J22") (pin "2") (pinfunction "2_2") (pintype "passive"))
      (node (ref "J22") (pin "3") (pinfunction "3_3") (pintype "passive"))
      (node (ref "J22") (pin "4") (pinfunction "4_4") (pintype "passive"))
      (node (ref "J22") (pin "5") (pinfunction "5_5") (pintype "passive"))
      (node (ref "J23") (pin "2") (pinfunction "2_2") (pintype "passive"))
      (node (ref "J23") (pin "3") (pinfunction "3_3") (pintype "passive"))
      (node (ref "J23") (pin "4") (pinfunction "4_4") (pintype "passive"))
      (node (ref "J23") (pin "5") (pinfunction "5_5") (pintype "passive"))
      (node (ref "J24") (pin "2") (pinfunction "2_2") (pintype "passive"))
      (node (ref "J24") (pin "3") (pinfunction "3_3") (pintype "passive"))
      (node (ref "J24") (pin "4") (pinfunction "4_4") (pintype "passive"))
      (node (ref "J24") (pin "5") (pinfunction "5_5") (pintype "passive"))
      (node (ref "J25") (pin "2") (pinfunction "2_2") (pintype "passive"))
      (node (ref "J25") (pin "3") (pinfunction "3_3") (pintype "passive"))
      (node (ref "J25") (pin "4") (pinfunction "4_4") (pintype "passive"))
      (node (ref "J25") (pin "5") (pinfunction "5_5") (pintype "passive"))
      (node (ref "J26") (pin "2") (pinfunction "2_2") (pintype "passive"))
      (node (ref "J26") (pin "3") (pinfunction "3_3") (pintype "passive"))
      (node (ref "J26") (pin "4") (pinfunction "4_4") (pintype "passive"))
      (node (ref "J26") (pin "5") (pinfunction "5_5") (pintype "passive"))
      (node (ref "J27") (pin "2") (pinfunction "2_2") (pintype "passive"))
      (node (ref "J27") (pin "3") (pinfunction "3_3") (pintype "passive"))
      (node (ref "J27") (pin "4") (pinfunction "4_4") (pintype "passive"))
      (node (ref "J27") (pin "5") (pinfunction "5_5") (pintype "passive"))
      (node (ref "J28") (pin "2") (pinfunction "2_2") (pintype "passive"))
      (node (ref "J28") (pin "3") (pinfunction "3_3") (pintype "passive"))
      (node (ref "J28") (pin "4") (pinfunction "4_4") (pintype "passive"))
      (node (ref "J28") (pin "5") (pinfunction "5_5") (pintype "passive"))
      (node (ref "J29") (pin "2") (pinfunction "2_2") (pintype "passive"))
      (node (ref "J29") (pin "3") (pinfunction "3_3") (pintype "passive"))
      (node (ref "J29") (pin "4") (pinfunction "4_4") (pintype "passive"))
      (node (ref "J29") (pin "5") (pinfunction "5_5") (pintype "passive"))
      (node (ref "J3") (pin "2") (pinfunction "2_2") (pintype "passive"))
      (node (ref "J3") (pin "3") (pinfunction "3_3") (pintype "passive"))
      (node (ref "J3") (pin "4") (pinfunction "4_4") (pintype "passive"))
      (node (ref "J3") (pin "5") (pinfunction "5_5") (pintype "passive"))
      (node (ref "J30") (pin "2") (pinfunction "2_2") (pintype "passive"))
      (node (ref "J30") (pin "3") (pinfunction "3_3") (pintype "passive"))
      (node (ref "J30") (pin "4") (pinfunction "4_4") (pintype "passive"))
      (node (ref "J30") (pin "5") (pinfunction "5_5") (pintype "passive"))
      (node (ref "J31") (pin "2") (pinfunction "2_2") (pintype "passive"))
      (node (ref "J31") (pin "3") (pinfunction "3_3") (pintype "passive"))
      (node (ref "J31") (pin "4") (pinfunction "4_4") (pintype "passive"))
      (node (ref "J31") (pin "5") (pinfunction "5_5") (pintype "passive"))
      (node (ref "J32") (pin "2") (pinfunction "2_2") (pintype "passive"))
      (node (ref "J32") (pin "3") (pinfunction "3_3") (pintype "passive"))
      (node (ref "J32") (pin "4") (pinfunction "4_4") (pintype "passive"))
      (node (ref "J32") (pin "5") (pinfunction "5_5") (pintype "passive"))
      (node (ref "J33") (pin "2") (pinfunction "2_2") (pintype "passive"))
      (node (ref "J33") (pin "3") (pinfunction "3_3") (pintype "passive"))
      (node (ref "J33") (pin "4") (pinfunction "4_4") (pintype "passive"))
      (node (ref "J33") (pin "5") (pinfunction "5_5") (pintype "passive"))
      (node (ref "J34") (pin "2") (pinfunction "2_2") (pintype "passive"))
      (node (ref "J34") (pin "3") (pinfunction "3_3") (pintype "passive"))
      (node (ref "J34") (pin "4") (pinfunction "4_4") (pintype "passive"))
      (node (ref "J34") (pin "5") (pinfunction "5_5") (pintype "passive"))
      (node (ref "J4") (pin "2") (pinfunction "2_2") (pintype "passive"))
      (node (ref "J4") (pin "3") (pinfunction "3_3") (pintype "passive"))
      (node (ref "J4") (pin "4") (pinfunction "4_4") (pintype "passive"))
      (node (ref "J4") (pin "5") (pinfunction "5_5") (pintype "passive"))
      (node (ref "J5") (pin "2") (pinfunction "2_2") (pintype "passive"))
      (node (ref "J5") (pin "3") (pinfunction "3_3") (pintype "passive"))
      (node (ref "J5") (pin "4") (pinfunction "4_4") (pintype "passive"))
      (node (ref "J5") (pin "5") (pinfunction "5_5") (pintype "passive"))
      (node (ref "J6") (pin "2") (pinfunction "2_2") (pintype "passive"))
      (node (ref "J6") (pin "3") (pinfunction "3_3") (pintype "passive"))
      (node (ref "J6") (pin "4") (pinfunction "4_4") (pintype "passive"))
      (node (ref "J6") (pin "5") (pinfunction "5_5") (pintype "passive"))
      (node (ref "J7") (pin "10") (pinfunction "10_10") (pintype "passive"))
      (node (ref "J7") (pin "100") (pinfunction "100_100") (pintype "passive"))
      (node (ref "J7") (pin "102") (pinfunction "102_102") (pintype "passive"))
      (node (ref "J7") (pin "104") (pinfunction "104_104") (pintype "passive"))
      (node (ref "J7") (pin "105") (pinfunction "105_105") (pintype "passive"))
      (node (ref "J7") (pin "106") (pinfunction "106_106") (pintype "passive"))
      (node (ref "J7") (pin "107") (pinfunction "107_107") (pintype "passive"))
      (node (ref "J7") (pin "108") (pinfunction "108_108") (pintype "passive"))
      (node (ref "J7") (pin "110") (pinfunction "110_110") (pintype "passive"))
      (node (ref "J7") (pin "112") (pinfunction "112_112") (pintype "passive"))
      (node (ref "J7") (pin "113") (pinfunction "113_113") (pintype "passive"))
      (node (ref "J7") (pin "114") (pinfunction "114_114") (pintype "passive"))
      (node (ref "J7") (pin "115") (pinfunction "115_115") (pintype "passive"))
      (node (ref "J7") (pin "116") (pinfunction "116_116") (pintype "passive"))
      (node (ref "J7") (pin "118") (pinfunction "118_118") (pintype "passive"))
      (node (ref "J7") (pin "12") (pinfunction "12_12") (pintype "passive"))
      (node (ref "J7") (pin "120") (pinfunction "120_120") (pintype "passive"))
      (node (ref "J7") (pin "13") (pinfunction "13_13") (pintype "passive"))
      (node (ref "J7") (pin "14") (pinfunction "14_14") (pintype "passive"))
      (node (ref "J7") (pin "15") (pinfunction "15_15") (pintype "passive"))
      (node (ref "J7") (pin "16") (pinfunction "16_16") (pintype "passive"))
      (node (ref "J7") (pin "18") (pinfunction "18_18") (pintype "passive"))
      (node (ref "J7") (pin "2") (pinfunction "2_2") (pintype "passive"))
      (node (ref "J7") (pin "20") (pinfunction "20_20") (pintype "passive"))
      (node (ref "J7") (pin "21") (pinfunction "21_21") (pintype "passive"))
      (node (ref "J7") (pin "22") (pinfunction "22_22") (pintype "passive"))
      (node (ref "J7") (pin "23") (pinfunction "23_23") (pintype "passive"))
      (node (ref "J7") (pin "24") (pinfunction "24_24") (pintype "passive"))
      (node (ref "J7") (pin "26") (pinfunction "26_26") (pintype "passive"))
      (node (ref "J7") (pin "28") (pinfunction "28_28") (pintype "passive"))
      (node (ref "J7") (pin "29") (pinfunction "29_29") (pintype "passive"))
      (node (ref "J7") (pin "30") (pinfunction "30_30") (pintype "passive"))
      (node (ref "J7") (pin "31") (pinfunction "31_31") (pintype "passive"))
      (node (ref "J7") (pin "32") (pinfunction "32_32") (pintype "passive"))
      (node (ref "J7") (pin "34") (pinfunction "34_34") (pintype "passive"))
      (node (ref "J7") (pin "36") (pinfunction "36_36") (pintype "passive"))
      (node (ref "J7") (pin "37") (pinfunction "37_37") (pintype "passive"))
      (node (ref "J7") (pin "38") (pinfunction "38_38") (pintype "passive"))
      (node (ref "J7") (pin "39") (pinfunction "39_39") (pintype "passive"))
      (node (ref "J7") (pin "4") (pinfunction "4_4") (pintype "passive"))
      (node (ref "J7") (pin "40") (pinfunction "40_40") (pintype "passive"))
      (node (ref "J7") (pin "42") (pinfunction "42_42") (pintype "passive"))
      (node (ref "J7") (pin "44") (pinfunction "44_44") (pintype "passive"))
      (node (ref "J7") (pin "45") (pinfunction "45_45") (pintype "passive"))
      (node (ref "J7") (pin "46") (pinfunction "46_46") (pintype "passive"))
      (node (ref "J7") (pin "47") (pinfunction "47_47") (pintype "passive"))
      (node (ref "J7") (pin "48") (pinfunction "48_48") (pintype "passive"))
      (node (ref "J7") (pin "5") (pinfunction "5_5") (pintype "passive"))
      (node (ref "J7") (pin "50") (pinfunction "50_50") (pintype "passive"))
      (node (ref "J7") (pin "52") (pinfunction "52_52") (pintype "passive"))
      (node (ref "J7") (pin "53") (pinfunction "53_53") (pintype "passive"))
      (node (ref "J7") (pin "54") (pinfunction "54_54") (pintype "passive"))
      (node (ref "J7") (pin "55") (pinfunction "55_55") (pintype "passive"))
      (node (ref "J7") (pin "56") (pinfunction "56_56") (pintype "passive"))
      (node (ref "J7") (pin "58") (pinfunction "58_58") (pintype "passive"))
      (node (ref "J7") (pin "6") (pinfunction "6_6") (pintype "passive"))
      (node (ref "J7") (pin "60") (pinfunction "60_60") (pintype "passive"))
      (node (ref "J7") (pin "62") (pinfunction "62_62") (pintype "passive"))
      (node (ref "J7") (pin "64") (pinfunction "64_64") (pintype "passive"))
      (node (ref "J7") (pin "65") (pinfunction "65_65") (pintype "passive"))
      (node (ref "J7") (pin "66") (pinfunction "66_66") (pintype "passive"))
      (node (ref "J7") (pin "67") (pinfunction "67_67") (pintype "passive"))
      (node (ref "J7") (pin "68") (pinfunction "68_68") (pintype "passive"))
      (node (ref "J7") (pin "7") (pinfunction "7_7") (pintype "passive"))
      (node (ref "J7") (pin "70") (pinfunction "70_70") (pintype "passive"))
      (node (ref "J7") (pin "72") (pinfunction "72_72") (pintype "passive"))
      (node (ref "J7") (pin "73") (pinfunction "73_73") (pintype "passive"))
      (node (ref "J7") (pin "74") (pinfunction "74_74") (pintype "passive"))
      (node (ref "J7") (pin "75") (pinfunction "75_75") (pintype "passive"))
      (node (ref "J7") (pin "76") (pinfunction "76_76") (pintype "passive"))
      (node (ref "J7") (pin "78") (pinfunction "78_78") (pintype "passive"))
      (node (ref "J7") (pin "8") (pinfunction "8_8") (pintype "passive"))
      (node (ref "J7") (pin "80") (pinfunction "80_80") (pintype "passive"))
      (node (ref "J7") (pin "81") (pinfunction "81_81") (pintype "passive"))
      (node (ref "J7") (pin "82") (pinfunction "82_82") (pintype "passive"))
      (node (ref "J7") (pin "83") (pinfunction "83_83") (pintype "passive"))
      (node (ref "J7") (pin "84") (pinfunction "84_84") (pintype "passive"))
      (node (ref "J7") (pin "86") (pinfunction "86_86") (pintype "passive"))
      (node (ref "J7") (pin "88") (pinfunction "88_88") (pintype "passive"))
      (node (ref "J7") (pin "89") (pinfunction "89_89") (pintype "passive"))
      (node (ref "J7") (pin "90") (pinfunction "90_90") (pintype "passive"))
      (node (ref "J7") (pin "91") (pinfunction "91_91") (pintype "passive"))
      (node (ref "J7") (pin "92") (pinfunction "92_92") (pintype "passive"))
      (node (ref "J7") (pin "94") (pinfunction "94_94") (pintype "passive"))
      (node (ref "J7") (pin "96") (pinfunction "96_96") (pintype "passive"))
      (node (ref "J7") (pin "97") (pinfunction "97_97") (pintype "passive"))
      (node (ref "J7") (pin "98") (pinfunction "98_98") (pintype "passive"))
      (node (ref "J7") (pin "99") (pinfunction "99_99") (pintype "passive"))
      (node (ref "J7") (pin "A1") (pinfunction "A1_A1") (pintype "power_in"))
      (node (ref "J7") (pin "A2") (pinfunction "A2_A2") (pintype "power_in"))
      (node (ref "J7") (pin "A3") (pinfunction "A3_A3") (pintype "power_in"))
      (node (ref "J7") (pin "A4") (pinfunction "A4_A4") (pintype "power_in"))
      (node (ref "J7") (pin "A5") (pinfunction "A5_A5") (pintype "power_in"))
      (node (ref "J7") (pin "A6") (pinfunction "A6_A6") (pintype "power_in"))
      (node (ref "J7") (pin "A7") (pinfunction "A7_A7") (pintype "power_in"))
      (node (ref "J7") (pin "A8") (pinfunction "A8_A8") (pintype "power_in"))
      (node (ref "J8") (pin "2") (pinfunction "2_2") (pintype "passive"))
      (node (ref "J8") (pin "3") (pinfunction "3_3") (pintype "passive"))
      (node (ref "J8") (pin "4") (pinfunction "4_4") (pintype "passive"))
      (node (ref "J8") (pin "5") (pinfunction "5_5") (pintype "passive"))
      (node (ref "J9") (pin "2") (pinfunction "2_2") (pintype "passive"))
      (node (ref "J9") (pin "3") (pinfunction "3_3") (pintype "passive"))
      (node (ref "J9") (pin "4") (pinfunction "4_4") (pintype "passive"))
      (node (ref "J9") (pin "5") (pinfunction "5_5") (pintype "passive"))
      (node (ref "R1") (pin "1") (pinfunction "1_1") (pintype "passive"))
      (node (ref "R10") (pin "1") (pinfunction "1_1") (pintype "passive"))
      (node (ref "R11") (pin "1") (pinfunction "1_1") (pintype "passive"))
      (node (ref "R12") (pin "1") (pinfunction "1_1") (pintype "passive"))
      (node (ref "R13") (pin "1") (pinfunction "1_1") (pintype "passive"))
      (node (ref "R14") (pin "1") (pinfunction "1_1") (pintype "passive"))
      (node (ref "R15") (pin "1") (pinfunction "1_1") (pintype "passive"))
      (node (ref "R16") (pin "1") (pinfunction "1_1") (pintype "passive"))
      (node (ref "R17") (pin "1") (pinfunction "1_1") (pintype "passive"))
      (node (ref "R18") (pin "1") (pinfunction "1_1") (pintype "passive"))
      (node (ref "R188") (pin "2") (pinfunction "2_2") (pintype "passive"))
      (node (ref "R189") (pin "2") (pinfunction "2_2") (pintype "passive"))
      (node (ref "R19") (pin "1") (pinfunction "1_1") (pintype "passive"))
      (node (ref "R2") (pin "1") (pinfunction "1_1") (pintype "passive"))
      (node (ref "R20") (pin "1") (pinfunction "1_1") (pintype "passive"))
      (node (ref "R21") (pin "1") (pinfunction "1_1") (pintype "passive"))
      (node (ref "R22") (pin "1") (pinfunction "1_1") (pintype "passive"))
      (node (ref "R23") (pin "1") (pinfunction "1_1") (pintype "passive"))
      (node (ref "R24") (pin "1") (pinfunction "1_1") (pintype "passive"))
      (node (ref "R25") (pin "1") (pinfunction "1_1") (pintype "passive"))
      (node (ref "R26") (pin "1") (pinfunction "1_1") (pintype "passive"))
      (node (ref "R27") (pin "1") (pinfunction "1_1") (pintype "passive"))
      (node (ref "R28") (pin "1") (pinfunction "1_1") (pintype "passive"))
      (node (ref "R29") (pin "1") (pinfunction "1_1") (pintype "passive"))
      (node (ref "R3") (pin "1") (pinfunction "1_1") (pintype "passive"))
      (node (ref "R30") (pin "1") (pinfunction "1_1") (pintype "passive"))
      (node (ref "R31") (pin "1") (pinfunction "1_1") (pintype "passive"))
      (node (ref "R32") (pin "1") (pinfunction "1_1") (pintype "passive"))
      (node (ref "R4") (pin "1") (pinfunction "1_1") (pintype "passive"))
      (node (ref "R5") (pin "1") (pinfunction "1_1") (pintype "passive"))
      (node (ref "R6") (pin "1") (pinfunction "1_1") (pintype "passive"))
      (node (ref "R7") (pin "1") (pinfunction "1_1") (pintype "passive"))
      (node (ref "R8") (pin "1") (pinfunction "1_1") (pintype "passive"))
      (node (ref "R9") (pin "1") (pinfunction "1_1") (pintype "passive"))
      (node (ref "T1") (pin "6") (pinfunction "6_6") (pintype "power_in"))
      (node (ref "TP31") (pin "1") (pintype "passive"))
      (node (ref "TP32") (pin "1") (pintype "passive"))
    )
    (net (code "101") (name "GND") (class "Default")
      (node (ref "R188") (pin "1") (pinfunction "1_1") (pintype "passive"))
      (node (ref "R189") (pin "1") (pinfunction "1_1") (pintype "passive"))
      (node (ref "T1") (pin "1") (pinfunction "1_1") (pintype "power_in"))
    )
    (net (code "102") (name "Net-(R33-Pad1)") (class "Default")
      (node (ref "R33") (pin "1") (pinfunction "1_1") (pintype "passive"))
      (node (ref "T1") (pin "4") (pinfunction "4_4") (pintype "power_in"))
    )
    (net (code "103") (name "unconnected-(T1-NC-Pad2)") (class "Default")
      (node (ref "T1") (pin "2") (pinfunction "NC_2") (pintype "passive+no_connect"))
    )
    (net (code "104") (name "unconnected-(T1-Pad5)") (class "Default")
      (node (ref "T1") (pin "5") (pinfunction "5_5") (pintype "power_in+no_connect"))
    )
  )
)
